# MusselGapeTracker_RevA_2.net
KiCad netlist of a schematic drawn in EAGLE
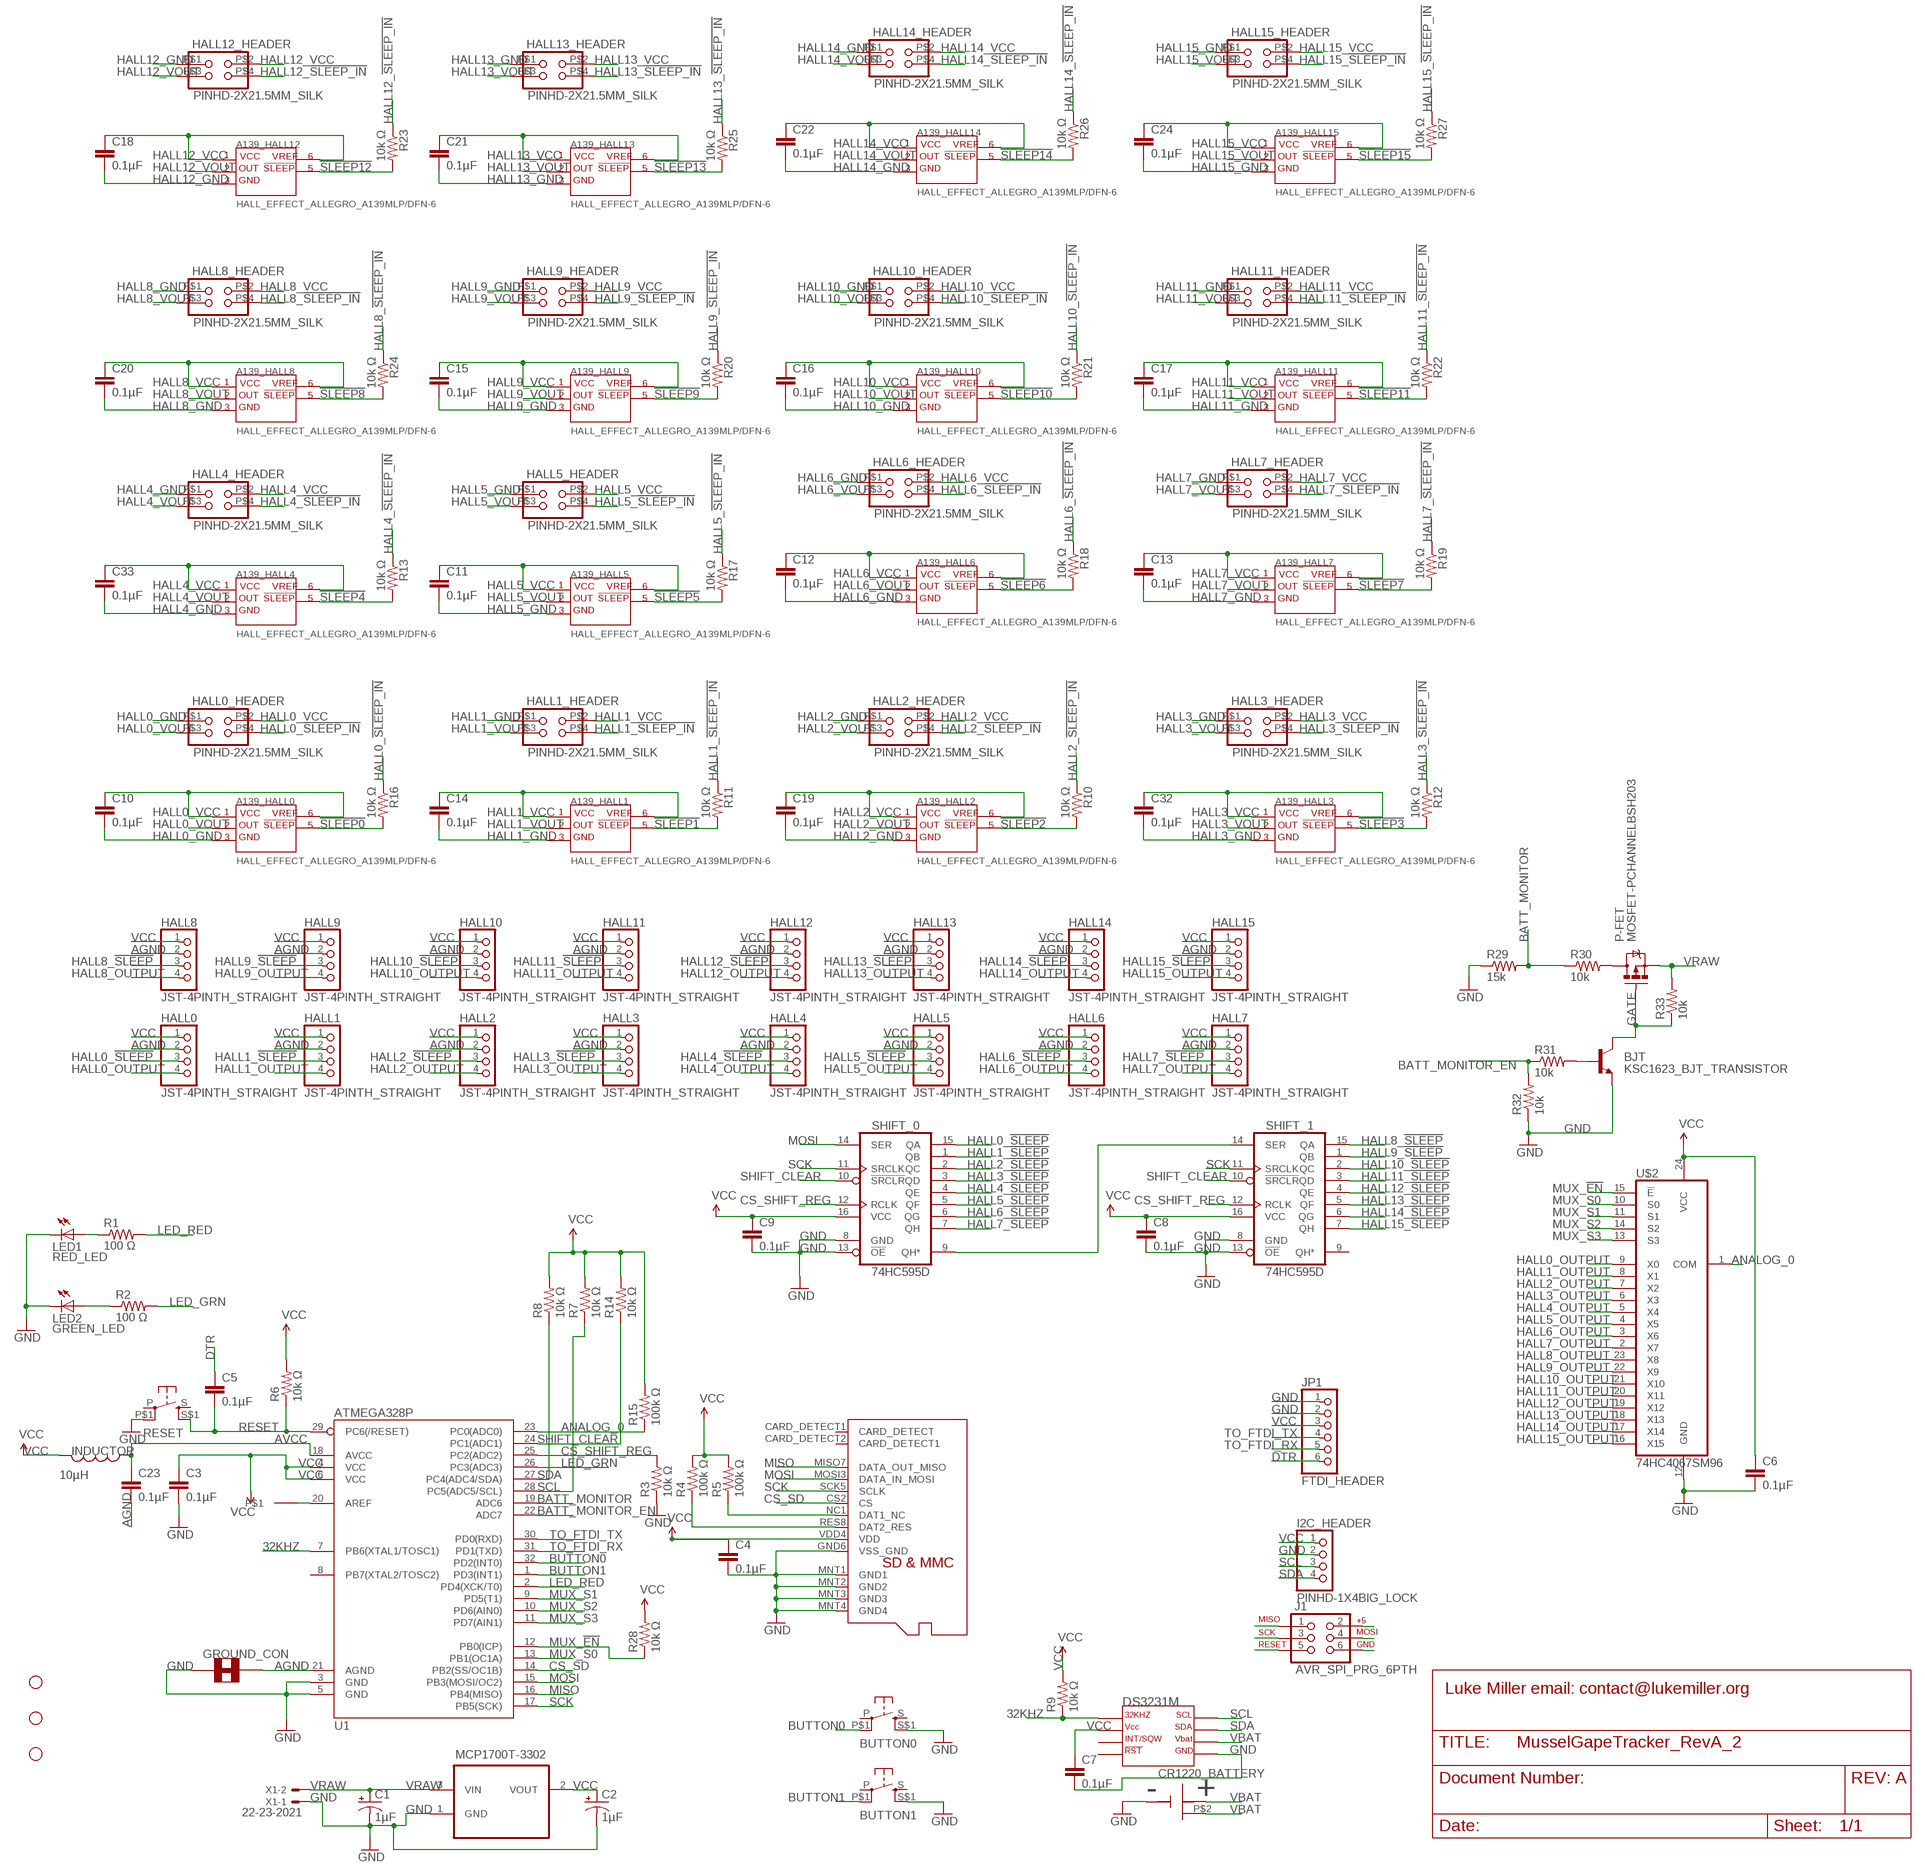
[diagram p0: schematic, sheet 1]

(export (version "E")
  (design (tool "Eeschema 10.0.6"))
  (components
    (comp (ref "A139_HALL0")
      (value "HALL_EFFECT_ALLEGRO_A139MLP/DFN-6")
      (footprint "eagle-import:A139__HALL_EFFECT")
      (libsource (lib "eagle-import") (part "HALL_EFFECT_ALLEGRO_A139MLP/DFN-6"))
    )
    (comp (ref "A139_HALL1")
      (value "HALL_EFFECT_ALLEGRO_A139MLP/DFN-6")
      (footprint "eagle-import:A139__HALL_EFFECT")
      (libsource (lib "eagle-import") (part "HALL_EFFECT_ALLEGRO_A139MLP/DFN-6"))
    )
    (comp (ref "A139_HALL2")
      (value "HALL_EFFECT_ALLEGRO_A139MLP/DFN-6")
      (footprint "eagle-import:A139__HALL_EFFECT")
      (libsource (lib "eagle-import") (part "HALL_EFFECT_ALLEGRO_A139MLP/DFN-6"))
    )
    (comp (ref "A139_HALL3")
      (value "HALL_EFFECT_ALLEGRO_A139MLP/DFN-6")
      (footprint "eagle-import:A139__HALL_EFFECT")
      (libsource (lib "eagle-import") (part "HALL_EFFECT_ALLEGRO_A139MLP/DFN-6"))
    )
    (comp (ref "A139_HALL4")
      (value "HALL_EFFECT_ALLEGRO_A139MLP/DFN-6")
      (footprint "eagle-import:A139__HALL_EFFECT")
      (libsource (lib "eagle-import") (part "HALL_EFFECT_ALLEGRO_A139MLP/DFN-6"))
    )
    (comp (ref "A139_HALL5")
      (value "HALL_EFFECT_ALLEGRO_A139MLP/DFN-6")
      (footprint "eagle-import:A139__HALL_EFFECT")
      (libsource (lib "eagle-import") (part "HALL_EFFECT_ALLEGRO_A139MLP/DFN-6"))
    )
    (comp (ref "A139_HALL6")
      (value "HALL_EFFECT_ALLEGRO_A139MLP/DFN-6")
      (footprint "eagle-import:A139__HALL_EFFECT")
      (libsource (lib "eagle-import") (part "HALL_EFFECT_ALLEGRO_A139MLP/DFN-6"))
    )
    (comp (ref "A139_HALL7")
      (value "HALL_EFFECT_ALLEGRO_A139MLP/DFN-6")
      (footprint "eagle-import:A139__HALL_EFFECT")
      (libsource (lib "eagle-import") (part "HALL_EFFECT_ALLEGRO_A139MLP/DFN-6"))
    )
    (comp (ref "A139_HALL8")
      (value "HALL_EFFECT_ALLEGRO_A139MLP/DFN-6")
      (footprint "eagle-import:A139__HALL_EFFECT")
      (libsource (lib "eagle-import") (part "HALL_EFFECT_ALLEGRO_A139MLP/DFN-6"))
    )
    (comp (ref "A139_HALL9")
      (value "HALL_EFFECT_ALLEGRO_A139MLP/DFN-6")
      (footprint "eagle-import:A139__HALL_EFFECT")
      (libsource (lib "eagle-import") (part "HALL_EFFECT_ALLEGRO_A139MLP/DFN-6"))
    )
    (comp (ref "A139_HALL10")
      (value "HALL_EFFECT_ALLEGRO_A139MLP/DFN-6")
      (footprint "eagle-import:A139__HALL_EFFECT")
      (libsource (lib "eagle-import") (part "HALL_EFFECT_ALLEGRO_A139MLP/DFN-6"))
    )
    (comp (ref "A139_HALL11")
      (value "HALL_EFFECT_ALLEGRO_A139MLP/DFN-6")
      (footprint "eagle-import:A139__HALL_EFFECT")
      (libsource (lib "eagle-import") (part "HALL_EFFECT_ALLEGRO_A139MLP/DFN-6"))
    )
    (comp (ref "A139_HALL12")
      (value "HALL_EFFECT_ALLEGRO_A139MLP/DFN-6")
      (footprint "eagle-import:A139__HALL_EFFECT")
      (libsource (lib "eagle-import") (part "HALL_EFFECT_ALLEGRO_A139MLP/DFN-6"))
    )
    (comp (ref "A139_HALL13")
      (value "HALL_EFFECT_ALLEGRO_A139MLP/DFN-6")
      (footprint "eagle-import:A139__HALL_EFFECT")
      (libsource (lib "eagle-import") (part "HALL_EFFECT_ALLEGRO_A139MLP/DFN-6"))
    )
    (comp (ref "A139_HALL14")
      (value "HALL_EFFECT_ALLEGRO_A139MLP/DFN-6")
      (footprint "eagle-import:A139__HALL_EFFECT")
      (libsource (lib "eagle-import") (part "HALL_EFFECT_ALLEGRO_A139MLP/DFN-6"))
    )
    (comp (ref "A139_HALL15")
      (value "HALL_EFFECT_ALLEGRO_A139MLP/DFN-6")
      (footprint "eagle-import:A139__HALL_EFFECT")
      (libsource (lib "eagle-import") (part "HALL_EFFECT_ALLEGRO_A139MLP/DFN-6"))
    )
    (comp (ref "BJT")
      (value "KSC1623_BJT_TRANSISTOR")
      (footprint "eagle-import:SOT23")
      (libsource (lib "eagle-import") (part "KSC1623_BJT_TRANSISTOR"))
    )
    (comp (ref "BUTTON0")
      (value "PUSHBUTTON_DPST_SMDSTANDARD")
      (footprint "eagle-import:PUSHBUTTON_DPST_SMD")
      (libsource (lib "eagle-import") (part "PUSHBUTTON_DPST_SMDSTANDARD"))
    )
    (comp (ref "BUTTON1")
      (value "PUSHBUTTON_DPST_SMDSTANDARD")
      (footprint "eagle-import:PUSHBUTTON_DPST_SMD")
      (libsource (lib "eagle-import") (part "PUSHBUTTON_DPST_SMDSTANDARD"))
    )
    (comp (ref "C1")
      (value "1µF")
      (footprint "eagle-import:PANASONIC_B")
      (libsource (lib "eagle-import") (part "CPOL-USB"))
    )
    (comp (ref "C2")
      (value "1µF")
      (footprint "eagle-import:PANASONIC_B")
      (libsource (lib "eagle-import") (part "CPOL-USB"))
    )
    (comp (ref "C3")
      (value "0.1µF")
      (footprint "eagle-import:0603")
      (libsource (lib "eagle-import") (part "CAP0603"))
    )
    (comp (ref "C4")
      (value "0.1µF")
      (footprint "eagle-import:0603")
      (libsource (lib "eagle-import") (part "CAP0603"))
    )
    (comp (ref "C5")
      (value "0.1µF")
      (footprint "eagle-import:0603")
      (libsource (lib "eagle-import") (part "CAP0603"))
    )
    (comp (ref "C6")
      (value "0.1µF")
      (footprint "eagle-import:0603")
      (libsource (lib "eagle-import") (part "CAP0603"))
    )
    (comp (ref "C7")
      (value "0.1µF")
      (footprint "eagle-import:0603")
      (libsource (lib "eagle-import") (part "CAP0603"))
    )
    (comp (ref "C8")
      (value "0.1µF")
      (footprint "eagle-import:0603")
      (libsource (lib "eagle-import") (part "CAP0603"))
    )
    (comp (ref "C9")
      (value "0.1µF")
      (footprint "eagle-import:0603")
      (libsource (lib "eagle-import") (part "CAP0603"))
    )
    (comp (ref "C10")
      (value "0.1µF")
      (footprint "eagle-import:0603")
      (libsource (lib "eagle-import") (part "CAP0603"))
    )
    (comp (ref "C11")
      (value "0.1µF")
      (footprint "eagle-import:0603")
      (libsource (lib "eagle-import") (part "CAP0603"))
    )
    (comp (ref "C12")
      (value "0.1µF")
      (footprint "eagle-import:0603")
      (libsource (lib "eagle-import") (part "CAP0603"))
    )
    (comp (ref "C13")
      (value "0.1µF")
      (footprint "eagle-import:0603")
      (libsource (lib "eagle-import") (part "CAP0603"))
    )
    (comp (ref "C14")
      (value "0.1µF")
      (footprint "eagle-import:0603")
      (libsource (lib "eagle-import") (part "CAP0603"))
    )
    (comp (ref "C15")
      (value "0.1µF")
      (footprint "eagle-import:0603")
      (libsource (lib "eagle-import") (part "CAP0603"))
    )
    (comp (ref "C16")
      (value "0.1µF")
      (footprint "eagle-import:0603")
      (libsource (lib "eagle-import") (part "CAP0603"))
    )
    (comp (ref "C17")
      (value "0.1µF")
      (footprint "eagle-import:0603")
      (libsource (lib "eagle-import") (part "CAP0603"))
    )
    (comp (ref "C18")
      (value "0.1µF")
      (footprint "eagle-import:0603")
      (libsource (lib "eagle-import") (part "CAP0603"))
    )
    (comp (ref "C19")
      (value "0.1µF")
      (footprint "eagle-import:0603")
      (libsource (lib "eagle-import") (part "CAP0603"))
    )
    (comp (ref "C20")
      (value "0.1µF")
      (footprint "eagle-import:0603")
      (libsource (lib "eagle-import") (part "CAP0603"))
    )
    (comp (ref "C21")
      (value "0.1µF")
      (footprint "eagle-import:0603")
      (libsource (lib "eagle-import") (part "CAP0603"))
    )
    (comp (ref "C22")
      (value "0.1µF")
      (footprint "eagle-import:0603")
      (libsource (lib "eagle-import") (part "CAP0603"))
    )
    (comp (ref "C23")
      (value "0.1µF")
      (footprint "eagle-import:0603")
      (libsource (lib "eagle-import") (part "CAP0603"))
    )
    (comp (ref "C24")
      (value "0.1µF")
      (footprint "eagle-import:0603")
      (libsource (lib "eagle-import") (part "CAP0603"))
    )
    (comp (ref "C32")
      (value "0.1µF")
      (footprint "eagle-import:0603")
      (libsource (lib "eagle-import") (part "CAP0603"))
    )
    (comp (ref "C33")
      (value "0.1µF")
      (footprint "eagle-import:0603")
      (libsource (lib "eagle-import") (part "CAP0603"))
    )
    (comp (ref "CR1220_BATTERY")
      (value "CR1220_BATTERY_HOLDERSMD")
      (footprint "eagle-import:CR1220_BATTERY_HOLDER_SMD")
      (libsource (lib "eagle-import") (part "CR1220_BATTERY_HOLDERSMD"))
    )
    (comp (ref "DS3231M")
      (value "DS3231MSOIC-8")
      (footprint "eagle-import:DS3231M_SOIC8")
      (libsource (lib "eagle-import") (part "DS3231MSOIC-8"))
    )
    (comp (ref "GROUND_CON")
      (value "SOLDER_JUMPER_TRACESTANDARD")
      (footprint "eagle-import:SJ_2S-TRACE")
      (libsource (lib "eagle-import") (part "SOLDER_JUMPER_TRACESTANDARD"))
    )
    (comp (ref "HALL0")
      (value "JST-4PINTH_STRAIGHT")
      (footprint "eagle-import:JST-PH-4-THM")
      (libsource (lib "eagle-import") (part "JST-4PINTH_STRAIGHT"))
    )
    (comp (ref "HALL0_HEADER")
      (value "PINHD-2X21.5MM_SILK")
      (footprint "eagle-import:2X2_1.5MM")
      (libsource (lib "eagle-import") (part "PINHD-2X21.5MM_SILK"))
    )
    (comp (ref "HALL1")
      (value "JST-4PINTH_STRAIGHT")
      (footprint "eagle-import:JST-PH-4-THM")
      (libsource (lib "eagle-import") (part "JST-4PINTH_STRAIGHT"))
    )
    (comp (ref "HALL1_HEADER")
      (value "PINHD-2X21.5MM_SILK")
      (footprint "eagle-import:2X2_1.5MM")
      (libsource (lib "eagle-import") (part "PINHD-2X21.5MM_SILK"))
    )
    (comp (ref "HALL2")
      (value "JST-4PINTH_STRAIGHT")
      (footprint "eagle-import:JST-PH-4-THM")
      (libsource (lib "eagle-import") (part "JST-4PINTH_STRAIGHT"))
    )
    (comp (ref "HALL2_HEADER")
      (value "PINHD-2X21.5MM_SILK")
      (footprint "eagle-import:2X2_1.5MM")
      (libsource (lib "eagle-import") (part "PINHD-2X21.5MM_SILK"))
    )
    (comp (ref "HALL3")
      (value "JST-4PINTH_STRAIGHT")
      (footprint "eagle-import:JST-PH-4-THM")
      (libsource (lib "eagle-import") (part "JST-4PINTH_STRAIGHT"))
    )
    (comp (ref "HALL3_HEADER")
      (value "PINHD-2X21.5MM_SILK")
      (footprint "eagle-import:2X2_1.5MM")
      (libsource (lib "eagle-import") (part "PINHD-2X21.5MM_SILK"))
    )
    (comp (ref "HALL4")
      (value "JST-4PINTH_STRAIGHT")
      (footprint "eagle-import:JST-PH-4-THM")
      (libsource (lib "eagle-import") (part "JST-4PINTH_STRAIGHT"))
    )
    (comp (ref "HALL4_HEADER")
      (value "PINHD-2X21.5MM_SILK")
      (footprint "eagle-import:2X2_1.5MM")
      (libsource (lib "eagle-import") (part "PINHD-2X21.5MM_SILK"))
    )
    (comp (ref "HALL5")
      (value "JST-4PINTH_STRAIGHT")
      (footprint "eagle-import:JST-PH-4-THM")
      (libsource (lib "eagle-import") (part "JST-4PINTH_STRAIGHT"))
    )
    (comp (ref "HALL5_HEADER")
      (value "PINHD-2X21.5MM_SILK")
      (footprint "eagle-import:2X2_1.5MM")
      (libsource (lib "eagle-import") (part "PINHD-2X21.5MM_SILK"))
    )
    (comp (ref "HALL6")
      (value "JST-4PINTH_STRAIGHT")
      (footprint "eagle-import:JST-PH-4-THM")
      (libsource (lib "eagle-import") (part "JST-4PINTH_STRAIGHT"))
    )
    (comp (ref "HALL6_HEADER")
      (value "PINHD-2X21.5MM_SILK")
      (footprint "eagle-import:2X2_1.5MM")
      (libsource (lib "eagle-import") (part "PINHD-2X21.5MM_SILK"))
    )
    (comp (ref "HALL7")
      (value "JST-4PINTH_STRAIGHT")
      (footprint "eagle-import:JST-PH-4-THM")
      (libsource (lib "eagle-import") (part "JST-4PINTH_STRAIGHT"))
    )
    (comp (ref "HALL7_HEADER")
      (value "PINHD-2X21.5MM_SILK")
      (footprint "eagle-import:2X2_1.5MM")
      (libsource (lib "eagle-import") (part "PINHD-2X21.5MM_SILK"))
    )
    (comp (ref "HALL8")
      (value "JST-4PINTH_STRAIGHT")
      (footprint "eagle-import:JST-PH-4-THM")
      (libsource (lib "eagle-import") (part "JST-4PINTH_STRAIGHT"))
    )
    (comp (ref "HALL8_HEADER")
      (value "PINHD-2X21.5MM_SILK")
      (footprint "eagle-import:2X2_1.5MM")
      (libsource (lib "eagle-import") (part "PINHD-2X21.5MM_SILK"))
    )
    (comp (ref "HALL9")
      (value "JST-4PINTH_STRAIGHT")
      (footprint "eagle-import:JST-PH-4-THM")
      (libsource (lib "eagle-import") (part "JST-4PINTH_STRAIGHT"))
    )
    (comp (ref "HALL9_HEADER")
      (value "PINHD-2X21.5MM_SILK")
      (footprint "eagle-import:2X2_1.5MM")
      (libsource (lib "eagle-import") (part "PINHD-2X21.5MM_SILK"))
    )
    (comp (ref "HALL10")
      (value "JST-4PINTH_STRAIGHT")
      (footprint "eagle-import:JST-PH-4-THM")
      (libsource (lib "eagle-import") (part "JST-4PINTH_STRAIGHT"))
    )
    (comp (ref "HALL10_HEADER")
      (value "PINHD-2X21.5MM_SILK")
      (footprint "eagle-import:2X2_1.5MM")
      (libsource (lib "eagle-import") (part "PINHD-2X21.5MM_SILK"))
    )
    (comp (ref "HALL11")
      (value "JST-4PINTH_STRAIGHT")
      (footprint "eagle-import:JST-PH-4-THM")
      (libsource (lib "eagle-import") (part "JST-4PINTH_STRAIGHT"))
    )
    (comp (ref "HALL11_HEADER")
      (value "PINHD-2X21.5MM_SILK")
      (footprint "eagle-import:2X2_1.5MM")
      (libsource (lib "eagle-import") (part "PINHD-2X21.5MM_SILK"))
    )
    (comp (ref "HALL12")
      (value "JST-4PINTH_STRAIGHT")
      (footprint "eagle-import:JST-PH-4-THM")
      (libsource (lib "eagle-import") (part "JST-4PINTH_STRAIGHT"))
    )
    (comp (ref "HALL12_HEADER")
      (value "PINHD-2X21.5MM_SILK")
      (footprint "eagle-import:2X2_1.5MM")
      (libsource (lib "eagle-import") (part "PINHD-2X21.5MM_SILK"))
    )
    (comp (ref "HALL13")
      (value "JST-4PINTH_STRAIGHT")
      (footprint "eagle-import:JST-PH-4-THM")
      (libsource (lib "eagle-import") (part "JST-4PINTH_STRAIGHT"))
    )
    (comp (ref "HALL13_HEADER")
      (value "PINHD-2X21.5MM_SILK")
      (footprint "eagle-import:2X2_1.5MM")
      (libsource (lib "eagle-import") (part "PINHD-2X21.5MM_SILK"))
    )
    (comp (ref "HALL14")
      (value "JST-4PINTH_STRAIGHT")
      (footprint "eagle-import:JST-PH-4-THM")
      (libsource (lib "eagle-import") (part "JST-4PINTH_STRAIGHT"))
    )
    (comp (ref "HALL14_HEADER")
      (value "PINHD-2X21.5MM_SILK")
      (footprint "eagle-import:2X2_1.5MM")
      (libsource (lib "eagle-import") (part "PINHD-2X21.5MM_SILK"))
    )
    (comp (ref "HALL15")
      (value "JST-4PINTH_STRAIGHT")
      (footprint "eagle-import:JST-PH-4-THM")
      (libsource (lib "eagle-import") (part "JST-4PINTH_STRAIGHT"))
    )
    (comp (ref "HALL15_HEADER")
      (value "PINHD-2X21.5MM_SILK")
      (footprint "eagle-import:2X2_1.5MM")
      (libsource (lib "eagle-import") (part "PINHD-2X21.5MM_SILK"))
    )
    (comp (ref "I2C_HEADER")
      (value "PINHD-1X4BIG_LOCK")
      (footprint "eagle-import:1X04_BIGLOCK")
      (libsource (lib "eagle-import") (part "PINHD-1X4BIG_LOCK"))
    )
    (comp (ref "INDUCTOR")
      (value "10µH")
      (footprint "eagle-import:I_0805")
      (libsource (lib "eagle-import") (part "INDUCTOR0805_TY"))
    )
    (comp (ref "J1")
      (value "AVR_SPI_PRG_6PTH")
      (footprint "eagle-import:2X3")
      (libsource (lib "eagle-import") (part "AVR_SPI_PRG_6PTH"))
    )
    (comp (ref "JP1")
      (value "FTDI_HEADER")
      (footprint "eagle-import:1X06-BIGLOCK")
      (libsource (lib "eagle-import") (part "PINHD-1X6LOCK"))
    )
    (comp (ref "LED1")
      (value "RED_LED")
      (footprint "eagle-import:CHIPLED_0805")
      (libsource (lib "eagle-import") (part "LED0805"))
    )
    (comp (ref "LED2")
      (value "GREEN_LED")
      (footprint "eagle-import:CHIPLED_0805")
      (libsource (lib "eagle-import") (part "LED0805"))
    )
    (comp (ref "MCP1700T-3302")
      (value "MCP1700T-3302E/TT")
      (footprint "eagle-import:SOT95P237X112-3N")
      (libsource (lib "eagle-import") (part "MCP1700T-3302E/TT"))
    )
    (comp (ref "P-FET")
      (value "MOSFET-PCHANNELBSH203")
      (footprint "eagle-import:SOT23-3")
      (libsource (lib "eagle-import") (part "MOSFET-PCHANNELBSH203"))
    )
    (comp (ref "R1")
      (value "100 Ω")
      (footprint "eagle-import:R0603")
      (libsource (lib "eagle-import") (part "RESISTOR_SMDR0603"))
    )
    (comp (ref "R2")
      (value "100 Ω")
      (footprint "eagle-import:R0603")
      (libsource (lib "eagle-import") (part "RESISTOR_SMDR0603"))
    )
    (comp (ref "R3")
      (value "10k Ω")
      (footprint "eagle-import:R0603")
      (libsource (lib "eagle-import") (part "RESISTOR_SMDR0603"))
    )
    (comp (ref "R4")
      (value "100k Ω")
      (footprint "eagle-import:R0603")
      (libsource (lib "eagle-import") (part "RESISTOR_SMDR0603"))
    )
    (comp (ref "R5")
      (value "100k Ω")
      (footprint "eagle-import:R0603")
      (libsource (lib "eagle-import") (part "RESISTOR_SMDR0603"))
    )
    (comp (ref "R6")
      (value "10k Ω")
      (footprint "eagle-import:R0603")
      (libsource (lib "eagle-import") (part "RESISTOR_SMDR0603"))
    )
    (comp (ref "R7")
      (value "10k Ω")
      (footprint "eagle-import:R0603")
      (libsource (lib "eagle-import") (part "RESISTOR_SMDR0603"))
    )
    (comp (ref "R8")
      (value "10k Ω")
      (footprint "eagle-import:R0603")
      (libsource (lib "eagle-import") (part "RESISTOR_SMDR0603"))
    )
    (comp (ref "R9")
      (value "10k Ω")
      (footprint "eagle-import:R0603")
      (libsource (lib "eagle-import") (part "RESISTOR_SMDR0603"))
    )
    (comp (ref "R10")
      (value "10k Ω")
      (footprint "eagle-import:R0603")
      (libsource (lib "eagle-import") (part "RESISTOR_SMDR0603"))
    )
    (comp (ref "R11")
      (value "10k Ω")
      (footprint "eagle-import:R0603")
      (libsource (lib "eagle-import") (part "RESISTOR_SMDR0603"))
    )
    (comp (ref "R12")
      (value "10k Ω")
      (footprint "eagle-import:R0603")
      (libsource (lib "eagle-import") (part "RESISTOR_SMDR0603"))
    )
    (comp (ref "R13")
      (value "10k Ω")
      (footprint "eagle-import:R0603")
      (libsource (lib "eagle-import") (part "RESISTOR_SMDR0603"))
    )
    (comp (ref "R14")
      (value "10k Ω")
      (footprint "eagle-import:R0603")
      (libsource (lib "eagle-import") (part "RESISTOR_SMDR0603"))
    )
    (comp (ref "R15")
      (value "100k Ω")
      (footprint "eagle-import:R0603")
      (libsource (lib "eagle-import") (part "RESISTOR_SMDR0603"))
    )
    (comp (ref "R16")
      (value "10k Ω")
      (footprint "eagle-import:R0603")
      (libsource (lib "eagle-import") (part "RESISTOR_SMDR0603"))
    )
    (comp (ref "R17")
      (value "10k Ω")
      (footprint "eagle-import:R0603")
      (libsource (lib "eagle-import") (part "RESISTOR_SMDR0603"))
    )
    (comp (ref "R18")
      (value "10k Ω")
      (footprint "eagle-import:R0603")
      (libsource (lib "eagle-import") (part "RESISTOR_SMDR0603"))
    )
    (comp (ref "R19")
      (value "10k Ω")
      (footprint "eagle-import:R0603")
      (libsource (lib "eagle-import") (part "RESISTOR_SMDR0603"))
    )
    (comp (ref "R20")
      (value "10k Ω")
      (footprint "eagle-import:R0603")
      (libsource (lib "eagle-import") (part "RESISTOR_SMDR0603"))
    )
    (comp (ref "R21")
      (value "10k Ω")
      (footprint "eagle-import:R0603")
      (libsource (lib "eagle-import") (part "RESISTOR_SMDR0603"))
    )
    (comp (ref "R22")
      (value "10k Ω")
      (footprint "eagle-import:R0603")
      (libsource (lib "eagle-import") (part "RESISTOR_SMDR0603"))
    )
    (comp (ref "R23")
      (value "10k Ω")
      (footprint "eagle-import:R0603")
      (libsource (lib "eagle-import") (part "RESISTOR_SMDR0603"))
    )
    (comp (ref "R24")
      (value "10k Ω")
      (footprint "eagle-import:R0603")
      (libsource (lib "eagle-import") (part "RESISTOR_SMDR0603"))
    )
    (comp (ref "R25")
      (value "10k Ω")
      (footprint "eagle-import:R0603")
      (libsource (lib "eagle-import") (part "RESISTOR_SMDR0603"))
    )
    (comp (ref "R26")
      (value "10k Ω")
      (footprint "eagle-import:R0603")
      (libsource (lib "eagle-import") (part "RESISTOR_SMDR0603"))
    )
    (comp (ref "R27")
      (value "10k Ω")
      (footprint "eagle-import:R0603")
      (libsource (lib "eagle-import") (part "RESISTOR_SMDR0603"))
    )
    (comp (ref "R28")
      (value "10k Ω")
      (footprint "eagle-import:R0603")
      (libsource (lib "eagle-import") (part "RESISTOR_SMDR0603"))
    )
    (comp (ref "R29")
      (value "15k")
      (footprint "eagle-import:R0603")
      (libsource (lib "eagle-import") (part "RESISTOR_SMDR0603"))
    )
    (comp (ref "R30")
      (value "10k")
      (footprint "eagle-import:R0603")
      (libsource (lib "eagle-import") (part "RESISTOR_SMDR0603"))
    )
    (comp (ref "R31")
      (value "10k")
      (footprint "eagle-import:R0603")
      (libsource (lib "eagle-import") (part "RESISTOR_SMDR0603"))
    )
    (comp (ref "R32")
      (value "10k")
      (footprint "eagle-import:R0603")
      (libsource (lib "eagle-import") (part "RESISTOR_SMDR0603"))
    )
    (comp (ref "R33")
      (value "10k")
      (footprint "eagle-import:R0603")
      (libsource (lib "eagle-import") (part "RESISTOR_SMDR0603"))
    )
    (comp (ref "RESET")
      (value "PUSHBUTTON_DPST_SMDSTANDARD")
      (footprint "eagle-import:PUSHBUTTON_DPST_SMD")
      (libsource (lib "eagle-import") (part "PUSHBUTTON_DPST_SMDSTANDARD"))
    )
    (comp (ref "SHIFT_0")
      (value "74HC595D")
      (footprint "eagle-import:SO16")
      (libsource (lib "eagle-import") (part "74HC595D"))
    )
    (comp (ref "SHIFT_1")
      (value "74HC595D")
      (footprint "eagle-import:SO16")
      (libsource (lib "eagle-import") (part "74HC595D"))
    )
    (comp (ref "STANDOFF1")
      (value "STAND-OFF")
      (footprint "eagle-import:STAND-OFF")
      (libsource (lib "eagle-import") (part "STAND-OFF"))
    )
    (comp (ref "STANDOFF2")
      (value "STAND-OFF")
      (footprint "eagle-import:STAND-OFF")
      (libsource (lib "eagle-import") (part "STAND-OFF"))
    )
    (comp (ref "STANDOFF3")
      (value "STAND-OFF")
      (footprint "eagle-import:STAND-OFF")
      (libsource (lib "eagle-import") (part "STAND-OFF"))
    )
    (comp (ref "U$1")
      (value "MICROSD_MOLEX_REVERSECURRENT")
      (footprint "eagle-import:MICROSD_SOCKET_MOLEX_REVERSEMOUNT")
      (libsource (lib "eagle-import") (part "MICROSD_MOLEX_REVERSECURRENT"))
    )
    (comp (ref "U$2")
      (value "74HC4067SM96")
      (footprint "eagle-import:SSOP24")
      (libsource (lib "eagle-import") (part "74HC4067SM96"))
    )
    (comp (ref "U$17")
      (value "PINHD-1X1SMALL")
      (footprint "eagle-import:1X01_SMALL")
      (libsource (lib "eagle-import") (part "PINHD-1X1SMALL"))
    )
    (comp (ref "U1")
      (value "ATMEGA328P")
      (footprint "eagle-import:TQFP32-08")
      (libsource (lib "eagle-import") (part "ATMEGA328_SMT"))
    )
    (comp (ref "X1")
      (value "22-23-2021")
      (footprint "eagle-import:22-23-2021")
      (fields (field (name "MF") "MOLEX"))
      (libsource (lib "eagle-import") (part "22-23-2021"))
    )
  )
  (nets
    (net (code "1") (name "/32KHZ") (class "Default")
      (node (ref "DS3231M") (pin "1") (pinfunction "P$1_32KHZ_1") (pintype "bidirectional"))
      (node (ref "R9") (pin "1") (pinfunction "1_1") (pintype "passive"))
      (node (ref "U1") (pin "7") (pinfunction "PB6(XTAL1/TOSC1)_7") (pintype "bidirectional"))
    )
    (net (code "2") (name "/AGND") (class "Default")
      (node (ref "C23") (pin "2") (pinfunction "2_2") (pintype "passive"))
      (node (ref "GROUND_CON") (pin "2") (pinfunction "P$2_2") (pintype "bidirectional"))
      (node (ref "HALL0") (pin "2") (pinfunction "2_2") (pintype "passive"))
      (node (ref "HALL1") (pin "2") (pinfunction "2_2") (pintype "passive"))
      (node (ref "HALL10") (pin "2") (pinfunction "2_2") (pintype "passive"))
      (node (ref "HALL11") (pin "2") (pinfunction "2_2") (pintype "passive"))
      (node (ref "HALL12") (pin "2") (pinfunction "2_2") (pintype "passive"))
      (node (ref "HALL13") (pin "2") (pinfunction "2_2") (pintype "passive"))
      (node (ref "HALL14") (pin "2") (pinfunction "2_2") (pintype "passive"))
      (node (ref "HALL15") (pin "2") (pinfunction "2_2") (pintype "passive"))
      (node (ref "HALL2") (pin "2") (pinfunction "2_2") (pintype "passive"))
      (node (ref "HALL3") (pin "2") (pinfunction "2_2") (pintype "passive"))
      (node (ref "HALL4") (pin "2") (pinfunction "2_2") (pintype "passive"))
      (node (ref "HALL5") (pin "2") (pinfunction "2_2") (pintype "passive"))
      (node (ref "HALL6") (pin "2") (pinfunction "2_2") (pintype "passive"))
      (node (ref "HALL7") (pin "2") (pinfunction "2_2") (pintype "passive"))
      (node (ref "HALL8") (pin "2") (pinfunction "2_2") (pintype "passive"))
      (node (ref "HALL9") (pin "2") (pinfunction "2_2") (pintype "passive"))
      (node (ref "U1") (pin "21") (pinfunction "AGND_21") (pintype "bidirectional"))
    )
    (net (code "3") (name "/ANALOG_0") (class "Default")
      (node (ref "R15") (pin "1") (pinfunction "1_1") (pintype "passive"))
      (node (ref "U$2") (pin "1") (pinfunction "COM_1") (pintype "output"))
      (node (ref "U1") (pin "23") (pinfunction "PC0(ADC0)_23") (pintype "bidirectional"))
    )
    (net (code "4") (name "/AVCC") (class "Default")
      (node (ref "C23") (pin "1") (pinfunction "1_1") (pintype "passive"))
      (node (ref "INDUCTOR") (pin "P$1") (pinfunction "1_P$1") (pintype "passive"))
      (node (ref "U1") (pin "18") (pinfunction "AVCC_18") (pintype "bidirectional"))
    )
    (net (code "5") (name "/BATT_MONITOR") (class "Default")
      (node (ref "R29") (pin "2") (pinfunction "2_2") (pintype "passive"))
      (node (ref "R30") (pin "1") (pinfunction "1_1") (pintype "passive"))
      (node (ref "U1") (pin "19") (pinfunction "ADC6_19") (pintype "bidirectional"))
    )
    (net (code "6") (name "/BATT_MONITOR_EN") (class "Default")
      (node (ref "R31") (pin "1") (pinfunction "1_1") (pintype "passive"))
      (node (ref "R32") (pin "2") (pinfunction "2_2") (pintype "passive"))
      (node (ref "U1") (pin "22") (pinfunction "ADC7_22") (pintype "bidirectional"))
    )
    (net (code "7") (name "/BUTTON0") (class "Default")
      (node (ref "BUTTON0") (pin "P$1") (pinfunction "P1_P$1") (pintype "passive"))
      (node (ref "U1") (pin "32") (pinfunction "PD2(INT0)_32") (pintype "bidirectional"))
    )
    (net (code "8") (name "/BUTTON1") (class "Default")
      (node (ref "BUTTON1") (pin "P$1") (pinfunction "P1_P$1") (pintype "passive"))
      (node (ref "U1") (pin "1") (pinfunction "PD3(INT1)_1") (pintype "bidirectional"))
    )
    (net (code "9") (name "/CS_SD") (class "Default")
      (node (ref "U$1") (pin "CS2") (pinfunction "CS_CS2") (pintype "input"))
      (node (ref "U1") (pin "14") (pinfunction "PB2(SS/OC1B)_14") (pintype "bidirectional"))
    )
    (net (code "10") (name "/CS_SHIFT_REG") (class "Default")
      (node (ref "R3") (pin "2") (pinfunction "2_2") (pintype "passive"))
      (node (ref "SHIFT_0") (pin "12") (pinfunction "RCLK_12") (pintype "input"))
      (node (ref "SHIFT_1") (pin "12") (pinfunction "RCLK_12") (pintype "input"))
      (node (ref "U1") (pin "25") (pinfunction "PC2(ADC2)_25") (pintype "bidirectional"))
    )
    (net (code "11") (name "/DTR") (class "Default")
      (node (ref "C5") (pin "1") (pinfunction "1_1") (pintype "passive"))
      (node (ref "JP1") (pin "6") (pinfunction "6_6") (pintype "passive"))
    )
    (net (code "12") (name "/GATE") (class "Default")
      (node (ref "BJT") (pin "3") (pinfunction "C_3") (pintype "passive"))
      (node (ref "P-FET") (pin "1") (pinfunction "G_1") (pintype "passive"))
      (node (ref "R33") (pin "1") (pinfunction "1_1") (pintype "passive"))
    )
    (net (code "13") (name "/HALL0_GND") (class "Default")
      (node (ref "A139_HALL0") (pin "P$3_4") (pinfunction "P$3_P$3_4") (pintype "bidirectional"))
      (node (ref "C10") (pin "2") (pinfunction "2_2") (pintype "passive"))
      (node (ref "HALL0_HEADER") (pin "P$1") (pinfunction "1_P$1") (pintype "passive"))
    )
    (net (code "14") (name "/HALL0_OUTPUT") (class "Default")
      (node (ref "HALL0") (pin "4") (pinfunction "4_4") (pintype "passive"))
      (node (ref "U$2") (pin "9") (pinfunction "X0_9") (pintype "input"))
    )
    (net (code "15") (name "/HALL0_VCC") (class "Default")
      (node (ref "A139_HALL0") (pin "P$1") (pinfunction "P$1_P$1") (pintype "bidirectional"))
      (node (ref "A139_HALL0") (pin "P$6") (pinfunction "P$6_P$6") (pintype "bidirectional"))
      (node (ref "C10") (pin "1") (pinfunction "1_1") (pintype "passive"))
      (node (ref "HALL0_HEADER") (pin "P$2") (pinfunction "2_P$2") (pintype "passive"))
    )
    (net (code "16") (name "/HALL0_VOUT") (class "Default")
      (node (ref "A139_HALL0") (pin "P$2") (pinfunction "P$2_P$2") (pintype "bidirectional"))
      (node (ref "HALL0_HEADER") (pin "P$3") (pinfunction "3_P$3") (pintype "passive"))
    )
    (net (code "17") (name "/HALL0_~{SLEEP_IN}") (class "Default")
      (node (ref "HALL0_HEADER") (pin "P$4") (pinfunction "4_P$4") (pintype "passive"))
      (node (ref "R16") (pin "1") (pinfunction "1_1") (pintype "passive"))
    )
    (net (code "18") (name "/HALL0_~{SLEEP}") (class "Default")
      (node (ref "HALL0") (pin "3") (pinfunction "3_3") (pintype "passive"))
      (node (ref "SHIFT_0") (pin "15") (pinfunction "QA_15") (pintype "tri_state"))
    )
    (net (code "19") (name "/HALL1_GND") (class "Default")
      (node (ref "A139_HALL1") (pin "P$3_4") (pinfunction "P$3_P$3_4") (pintype "bidirectional"))
      (node (ref "C14") (pin "2") (pinfunction "2_2") (pintype "passive"))
      (node (ref "HALL1_HEADER") (pin "P$1") (pinfunction "1_P$1") (pintype "passive"))
    )
    (net (code "20") (name "/HALL1_OUTPUT") (class "Default")
      (node (ref "HALL1") (pin "4") (pinfunction "4_4") (pintype "passive"))
      (node (ref "U$2") (pin "8") (pinfunction "X1_8") (pintype "input"))
    )
    (net (code "21") (name "/HALL1_VCC") (class "Default")
      (node (ref "A139_HALL1") (pin "P$1") (pinfunction "P$1_P$1") (pintype "bidirectional"))
      (node (ref "A139_HALL1") (pin "P$6") (pinfunction "P$6_P$6") (pintype "bidirectional"))
      (node (ref "C14") (pin "1") (pinfunction "1_1") (pintype "passive"))
      (node (ref "HALL1_HEADER") (pin "P$2") (pinfunction "2_P$2") (pintype "passive"))
    )
    (net (code "22") (name "/HALL1_VOUT") (class "Default")
      (node (ref "A139_HALL1") (pin "P$2") (pinfunction "P$2_P$2") (pintype "bidirectional"))
      (node (ref "HALL1_HEADER") (pin "P$3") (pinfunction "3_P$3") (pintype "passive"))
    )
    (net (code "23") (name "/HALL1_~{SLEEP_IN}") (class "Default")
      (node (ref "HALL1_HEADER") (pin "P$4") (pinfunction "4_P$4") (pintype "passive"))
      (node (ref "R11") (pin "1") (pinfunction "1_1") (pintype "passive"))
    )
    (net (code "24") (name "/HALL1_~{SLEEP}") (class "Default")
      (node (ref "HALL1") (pin "3") (pinfunction "3_3") (pintype "passive"))
      (node (ref "SHIFT_0") (pin "1") (pinfunction "QB_1") (pintype "tri_state"))
    )
    (net (code "25") (name "/HALL2_GND") (class "Default")
      (node (ref "A139_HALL2") (pin "P$3_4") (pinfunction "P$3_P$3_4") (pintype "bidirectional"))
      (node (ref "C19") (pin "2") (pinfunction "2_2") (pintype "passive"))
      (node (ref "HALL2_HEADER") (pin "P$1") (pinfunction "1_P$1") (pintype "passive"))
    )
    (net (code "26") (name "/HALL2_OUTPUT") (class "Default")
      (node (ref "HALL2") (pin "4") (pinfunction "4_4") (pintype "passive"))
      (node (ref "U$2") (pin "7") (pinfunction "X2_7") (pintype "input"))
    )
    (net (code "27") (name "/HALL2_VCC") (class "Default")
      (node (ref "A139_HALL2") (pin "P$1") (pinfunction "P$1_P$1") (pintype "bidirectional"))
      (node (ref "A139_HALL2") (pin "P$6") (pinfunction "P$6_P$6") (pintype "bidirectional"))
      (node (ref "C19") (pin "1") (pinfunction "1_1") (pintype "passive"))
      (node (ref "HALL2_HEADER") (pin "P$2") (pinfunction "2_P$2") (pintype "passive"))
    )
    (net (code "28") (name "/HALL2_VOUT") (class "Default")
      (node (ref "A139_HALL2") (pin "P$2") (pinfunction "P$2_P$2") (pintype "bidirectional"))
      (node (ref "HALL2_HEADER") (pin "P$3") (pinfunction "3_P$3") (pintype "passive"))
    )
    (net (code "29") (name "/HALL2_~{SLEEP_IN}") (class "Default")
      (node (ref "HALL2_HEADER") (pin "P$4") (pinfunction "4_P$4") (pintype "passive"))
      (node (ref "R10") (pin "1") (pinfunction "1_1") (pintype "passive"))
    )
    (net (code "30") (name "/HALL2_~{SLEEP}") (class "Default")
      (node (ref "HALL2") (pin "3") (pinfunction "3_3") (pintype "passive"))
      (node (ref "SHIFT_0") (pin "2") (pinfunction "QC_2") (pintype "tri_state"))
    )
    (net (code "31") (name "/HALL3_GND") (class "Default")
      (node (ref "A139_HALL3") (pin "P$3_4") (pinfunction "P$3_P$3_4") (pintype "bidirectional"))
      (node (ref "C32") (pin "2") (pinfunction "2_2") (pintype "passive"))
      (node (ref "HALL3_HEADER") (pin "P$1") (pinfunction "1_P$1") (pintype "passive"))
    )
    (net (code "32") (name "/HALL3_OUTPUT") (class "Default")
      (node (ref "HALL3") (pin "4") (pinfunction "4_4") (pintype "passive"))
      (node (ref "U$2") (pin "6") (pinfunction "X3_6") (pintype "input"))
    )
    (net (code "33") (name "/HALL3_VCC") (class "Default")
      (node (ref "A139_HALL3") (pin "P$1") (pinfunction "P$1_P$1") (pintype "bidirectional"))
      (node (ref "A139_HALL3") (pin "P$6") (pinfunction "P$6_P$6") (pintype "bidirectional"))
      (node (ref "C32") (pin "1") (pinfunction "1_1") (pintype "passive"))
      (node (ref "HALL3_HEADER") (pin "P$2") (pinfunction "2_P$2") (pintype "passive"))
    )
    (net (code "34") (name "/HALL3_VOUT") (class "Default")
      (node (ref "A139_HALL3") (pin "P$2") (pinfunction "P$2_P$2") (pintype "bidirectional"))
      (node (ref "HALL3_HEADER") (pin "P$3") (pinfunction "3_P$3") (pintype "passive"))
    )
    (net (code "35") (name "/HALL3_~{SLEEP_IN}") (class "Default")
      (node (ref "HALL3_HEADER") (pin "P$4") (pinfunction "4_P$4") (pintype "passive"))
      (node (ref "R12") (pin "1") (pinfunction "1_1") (pintype "passive"))
    )
    (net (code "36") (name "/HALL3_~{SLEEP}") (class "Default")
      (node (ref "HALL3") (pin "3") (pinfunction "3_3") (pintype "passive"))
      (node (ref "SHIFT_0") (pin "3") (pinfunction "QD_3") (pintype "tri_state"))
    )
    (net (code "37") (name "/HALL4_GND") (class "Default")
      (node (ref "A139_HALL4") (pin "P$3_4") (pinfunction "P$3_P$3_4") (pintype "bidirectional"))
      (node (ref "C33") (pin "2") (pinfunction "2_2") (pintype "passive"))
      (node (ref "HALL4_HEADER") (pin "P$1") (pinfunction "1_P$1") (pintype "passive"))
    )
    (net (code "38") (name "/HALL4_OUTPUT") (class "Default")
      (node (ref "HALL4") (pin "4") (pinfunction "4_4") (pintype "passive"))
      (node (ref "U$2") (pin "5") (pinfunction "X4_5") (pintype "input"))
    )
    (net (code "39") (name "/HALL4_VCC") (class "Default")
      (node (ref "A139_HALL4") (pin "P$1") (pinfunction "P$1_P$1") (pintype "bidirectional"))
      (node (ref "A139_HALL4") (pin "P$6") (pinfunction "P$6_P$6") (pintype "bidirectional"))
      (node (ref "C33") (pin "1") (pinfunction "1_1") (pintype "passive"))
      (node (ref "HALL4_HEADER") (pin "P$2") (pinfunction "2_P$2") (pintype "passive"))
    )
    (net (code "40") (name "/HALL4_VOUT") (class "Default")
      (node (ref "A139_HALL4") (pin "P$2") (pinfunction "P$2_P$2") (pintype "bidirectional"))
      (node (ref "HALL4_HEADER") (pin "P$3") (pinfunction "3_P$3") (pintype "passive"))
    )
    (net (code "41") (name "/HALL4_~{SLEEP_IN}") (class "Default")
      (node (ref "HALL4_HEADER") (pin "P$4") (pinfunction "4_P$4") (pintype "passive"))
      (node (ref "R13") (pin "1") (pinfunction "1_1") (pintype "passive"))
    )
    (net (code "42") (name "/HALL4_~{SLEEP}") (class "Default")
      (node (ref "HALL4") (pin "3") (pinfunction "3_3") (pintype "passive"))
      (node (ref "SHIFT_0") (pin "4") (pinfunction "QE_4") (pintype "tri_state"))
    )
    (net (code "43") (name "/HALL5_GND") (class "Default")
      (node (ref "A139_HALL5") (pin "P$3_4") (pinfunction "P$3_P$3_4") (pintype "bidirectional"))
      (node (ref "C11") (pin "2") (pinfunction "2_2") (pintype "passive"))
      (node (ref "HALL5_HEADER") (pin "P$1") (pinfunction "1_P$1") (pintype "passive"))
    )
    (net (code "44") (name "/HALL5_OUTPUT") (class "Default")
      (node (ref "HALL5") (pin "4") (pinfunction "4_4") (pintype "passive"))
      (node (ref "U$2") (pin "4") (pinfunction "X5_4") (pintype "input"))
    )
    (net (code "45") (name "/HALL5_VCC") (class "Default")
      (node (ref "A139_HALL5") (pin "P$1") (pinfunction "P$1_P$1") (pintype "bidirectional"))
      (node (ref "A139_HALL5") (pin "P$6") (pinfunction "P$6_P$6") (pintype "bidirectional"))
      (node (ref "C11") (pin "1") (pinfunction "1_1") (pintype "passive"))
      (node (ref "HALL5_HEADER") (pin "P$2") (pinfunction "2_P$2") (pintype "passive"))
    )
    (net (code "46") (name "/HALL5_VOUT") (class "Default")
      (node (ref "A139_HALL5") (pin "P$2") (pinfunction "P$2_P$2") (pintype "bidirectional"))
      (node (ref "HALL5_HEADER") (pin "P$3") (pinfunction "3_P$3") (pintype "passive"))
    )
    (net (code "47") (name "/HALL5_~{SLEEP_IN}") (class "Default")
      (node (ref "HALL5_HEADER") (pin "P$4") (pinfunction "4_P$4") (pintype "passive"))
      (node (ref "R17") (pin "1") (pinfunction "1_1") (pintype "passive"))
    )
    (net (code "48") (name "/HALL5_~{SLEEP}") (class "Default")
      (node (ref "HALL5") (pin "3") (pinfunction "3_3") (pintype "passive"))
      (node (ref "SHIFT_0") (pin "5") (pinfunction "QF_5") (pintype "tri_state"))
    )
    (net (code "49") (name "/HALL6_GND") (class "Default")
      (node (ref "A139_HALL6") (pin "P$3_4") (pinfunction "P$3_P$3_4") (pintype "bidirectional"))
      (node (ref "C12") (pin "2") (pinfunction "2_2") (pintype "passive"))
      (node (ref "HALL6_HEADER") (pin "P$1") (pinfunction "1_P$1") (pintype "passive"))
    )
    (net (code "50") (name "/HALL6_OUTPUT") (class "Default")
      (node (ref "HALL6") (pin "4") (pinfunction "4_4") (pintype "passive"))
      (node (ref "U$2") (pin "3") (pinfunction "X6_3") (pintype "input"))
    )
    (net (code "51") (name "/HALL6_VCC") (class "Default")
      (node (ref "A139_HALL6") (pin "P$1") (pinfunction "P$1_P$1") (pintype "bidirectional"))
      (node (ref "A139_HALL6") (pin "P$6") (pinfunction "P$6_P$6") (pintype "bidirectional"))
      (node (ref "C12") (pin "1") (pinfunction "1_1") (pintype "passive"))
      (node (ref "HALL6_HEADER") (pin "P$2") (pinfunction "2_P$2") (pintype "passive"))
    )
    (net (code "52") (name "/HALL6_VOUT") (class "Default")
      (node (ref "A139_HALL6") (pin "P$2") (pinfunction "P$2_P$2") (pintype "bidirectional"))
      (node (ref "HALL6_HEADER") (pin "P$3") (pinfunction "3_P$3") (pintype "passive"))
    )
    (net (code "53") (name "/HALL6_~{SLEEP_IN}") (class "Default")
      (node (ref "HALL6_HEADER") (pin "P$4") (pinfunction "4_P$4") (pintype "passive"))
      (node (ref "R18") (pin "1") (pinfunction "1_1") (pintype "passive"))
    )
    (net (code "54") (name "/HALL6_~{SLEEP}") (class "Default")
      (node (ref "HALL6") (pin "3") (pinfunction "3_3") (pintype "passive"))
      (node (ref "SHIFT_0") (pin "6") (pinfunction "QG_6") (pintype "tri_state"))
    )
    (net (code "55") (name "/HALL7_GND") (class "Default")
      (node (ref "A139_HALL7") (pin "P$3_4") (pinfunction "P$3_P$3_4") (pintype "bidirectional"))
      (node (ref "C13") (pin "2") (pinfunction "2_2") (pintype "passive"))
      (node (ref "HALL7_HEADER") (pin "P$1") (pinfunction "1_P$1") (pintype "passive"))
    )
    (net (code "56") (name "/HALL7_OUTPUT") (class "Default")
      (node (ref "HALL7") (pin "4") (pinfunction "4_4") (pintype "passive"))
      (node (ref "U$2") (pin "2") (pinfunction "X7_2") (pintype "input"))
    )
    (net (code "57") (name "/HALL7_VCC") (class "Default")
      (node (ref "A139_HALL7") (pin "P$1") (pinfunction "P$1_P$1") (pintype "bidirectional"))
      (node (ref "A139_HALL7") (pin "P$6") (pinfunction "P$6_P$6") (pintype "bidirectional"))
      (node (ref "C13") (pin "1") (pinfunction "1_1") (pintype "passive"))
      (node (ref "HALL7_HEADER") (pin "P$2") (pinfunction "2_P$2") (pintype "passive"))
    )
    (net (code "58") (name "/HALL7_VOUT") (class "Default")
      (node (ref "A139_HALL7") (pin "P$2") (pinfunction "P$2_P$2") (pintype "bidirectional"))
      (node (ref "HALL7_HEADER") (pin "P$3") (pinfunction "3_P$3") (pintype "passive"))
    )
    (net (code "59") (name "/HALL7_~{SLEEP_IN}") (class "Default")
      (node (ref "HALL7_HEADER") (pin "P$4") (pinfunction "4_P$4") (pintype "passive"))
      (node (ref "R19") (pin "1") (pinfunction "1_1") (pintype "passive"))
    )
    (net (code "60") (name "/HALL7_~{SLEEP}") (class "Default")
      (node (ref "HALL7") (pin "3") (pinfunction "3_3") (pintype "passive"))
      (node (ref "SHIFT_0") (pin "7") (pinfunction "QH_7") (pintype "tri_state"))
    )
    (net (code "61") (name "/HALL8_GND") (class "Default")
      (node (ref "A139_HALL8") (pin "P$3_4") (pinfunction "P$3_P$3_4") (pintype "bidirectional"))
      (node (ref "C20") (pin "2") (pinfunction "2_2") (pintype "passive"))
      (node (ref "HALL8_HEADER") (pin "P$1") (pinfunction "1_P$1") (pintype "passive"))
    )
    (net (code "62") (name "/HALL8_OUTPUT") (class "Default")
      (node (ref "HALL8") (pin "4") (pinfunction "4_4") (pintype "passive"))
      (node (ref "U$2") (pin "23") (pinfunction "X8_23") (pintype "input"))
    )
    (net (code "63") (name "/HALL8_VCC") (class "Default")
      (node (ref "A139_HALL8") (pin "P$1") (pinfunction "P$1_P$1") (pintype "bidirectional"))
      (node (ref "A139_HALL8") (pin "P$6") (pinfunction "P$6_P$6") (pintype "bidirectional"))
      (node (ref "C20") (pin "1") (pinfunction "1_1") (pintype "passive"))
      (node (ref "HALL8_HEADER") (pin "P$2") (pinfunction "2_P$2") (pintype "passive"))
    )
    (net (code "64") (name "/HALL8_VOUT") (class "Default")
      (node (ref "A139_HALL8") (pin "P$2") (pinfunction "P$2_P$2") (pintype "bidirectional"))
      (node (ref "HALL8_HEADER") (pin "P$3") (pinfunction "3_P$3") (pintype "passive"))
    )
    (net (code "65") (name "/HALL8_~{SLEEP_IN}") (class "Default")
      (node (ref "HALL8_HEADER") (pin "P$4") (pinfunction "4_P$4") (pintype "passive"))
      (node (ref "R24") (pin "1") (pinfunction "1_1") (pintype "passive"))
    )
    (net (code "66") (name "/HALL8_~{SLEEP}") (class "Default")
      (node (ref "HALL8") (pin "3") (pinfunction "3_3") (pintype "passive"))
      (node (ref "SHIFT_1") (pin "15") (pinfunction "QA_15") (pintype "tri_state"))
    )
    (net (code "67") (name "/HALL9_GND") (class "Default")
      (node (ref "A139_HALL9") (pin "P$3_4") (pinfunction "P$3_P$3_4") (pintype "bidirectional"))
      (node (ref "C15") (pin "2") (pinfunction "2_2") (pintype "passive"))
      (node (ref "HALL9_HEADER") (pin "P$1") (pinfunction "1_P$1") (pintype "passive"))
    )
    (net (code "68") (name "/HALL9_OUTPUT") (class "Default")
      (node (ref "HALL9") (pin "4") (pinfunction "4_4") (pintype "passive"))
      (node (ref "U$2") (pin "22") (pinfunction "X9_22") (pintype "input"))
    )
    (net (code "69") (name "/HALL9_VCC") (class "Default")
      (node (ref "A139_HALL9") (pin "P$1") (pinfunction "P$1_P$1") (pintype "bidirectional"))
      (node (ref "A139_HALL9") (pin "P$6") (pinfunction "P$6_P$6") (pintype "bidirectional"))
      (node (ref "C15") (pin "1") (pinfunction "1_1") (pintype "passive"))
      (node (ref "HALL9_HEADER") (pin "P$2") (pinfunction "2_P$2") (pintype "passive"))
    )
    (net (code "70") (name "/HALL9_VOUT") (class "Default")
      (node (ref "A139_HALL9") (pin "P$2") (pinfunction "P$2_P$2") (pintype "bidirectional"))
      (node (ref "HALL9_HEADER") (pin "P$3") (pinfunction "3_P$3") (pintype "passive"))
    )
    (net (code "71") (name "/HALL9_~{SLEEP_IN}") (class "Default")
      (node (ref "HALL9_HEADER") (pin "P$4") (pinfunction "4_P$4") (pintype "passive"))
      (node (ref "R20") (pin "1") (pinfunction "1_1") (pintype "passive"))
    )
    (net (code "72") (name "/HALL9_~{SLEEP}") (class "Default")
      (node (ref "HALL9") (pin "3") (pinfunction "3_3") (pintype "passive"))
      (node (ref "SHIFT_1") (pin "1") (pinfunction "QB_1") (pintype "tri_state"))
    )
    (net (code "73") (name "/HALL10_GND") (class "Default")
      (node (ref "A139_HALL10") (pin "P$3_4") (pinfunction "P$3_P$3_4") (pintype "bidirectional"))
      (node (ref "C16") (pin "2") (pinfunction "2_2") (pintype "passive"))
      (node (ref "HALL10_HEADER") (pin "P$1") (pinfunction "1_P$1") (pintype "passive"))
    )
    (net (code "74") (name "/HALL10_OUTPUT") (class "Default")
      (node (ref "HALL10") (pin "4") (pinfunction "4_4") (pintype "passive"))
      (node (ref "U$2") (pin "21") (pinfunction "X10_21") (pintype "input"))
    )
    (net (code "75") (name "/HALL10_VCC") (class "Default")
      (node (ref "A139_HALL10") (pin "P$1") (pinfunction "P$1_P$1") (pintype "bidirectional"))
      (node (ref "A139_HALL10") (pin "P$6") (pinfunction "P$6_P$6") (pintype "bidirectional"))
      (node (ref "C16") (pin "1") (pinfunction "1_1") (pintype "passive"))
      (node (ref "HALL10_HEADER") (pin "P$2") (pinfunction "2_P$2") (pintype "passive"))
    )
    (net (code "76") (name "/HALL10_VOUT") (class "Default")
      (node (ref "A139_HALL10") (pin "P$2") (pinfunction "P$2_P$2") (pintype "bidirectional"))
      (node (ref "HALL10_HEADER") (pin "P$3") (pinfunction "3_P$3") (pintype "passive"))
    )
    (net (code "77") (name "/HALL10_~{SLEEP_IN}") (class "Default")
      (node (ref "HALL10_HEADER") (pin "P$4") (pinfunction "4_P$4") (pintype "passive"))
      (node (ref "R21") (pin "1") (pinfunction "1_1") (pintype "passive"))
    )
    (net (code "78") (name "/HALL10_~{SLEEP}") (class "Default")
      (node (ref "HALL10") (pin "3") (pinfunction "3_3") (pintype "passive"))
      (node (ref "SHIFT_1") (pin "2") (pinfunction "QC_2") (pintype "tri_state"))
    )
    (net (code "79") (name "/HALL11_GND") (class "Default")
      (node (ref "A139_HALL11") (pin "P$3_4") (pinfunction "P$3_P$3_4") (pintype "bidirectional"))
      (node (ref "C17") (pin "2") (pinfunction "2_2") (pintype "passive"))
      (node (ref "HALL11_HEADER") (pin "P$1") (pinfunction "1_P$1") (pintype "passive"))
    )
    (net (code "80") (name "/HALL11_OUTPUT") (class "Default")
      (node (ref "HALL11") (pin "4") (pinfunction "4_4") (pintype "passive"))
      (node (ref "U$2") (pin "20") (pinfunction "X11_20") (pintype "input"))
    )
    (net (code "81") (name "/HALL11_VCC") (class "Default")
      (node (ref "A139_HALL11") (pin "P$1") (pinfunction "P$1_P$1") (pintype "bidirectional"))
      (node (ref "A139_HALL11") (pin "P$6") (pinfunction "P$6_P$6") (pintype "bidirectional"))
      (node (ref "C17") (pin "1") (pinfunction "1_1") (pintype "passive"))
      (node (ref "HALL11_HEADER") (pin "P$2") (pinfunction "2_P$2") (pintype "passive"))
    )
    (net (code "82") (name "/HALL11_VOUT") (class "Default")
      (node (ref "A139_HALL11") (pin "P$2") (pinfunction "P$2_P$2") (pintype "bidirectional"))
      (node (ref "HALL11_HEADER") (pin "P$3") (pinfunction "3_P$3") (pintype "passive"))
    )
    (net (code "83") (name "/HALL11_~{SLEEP_IN}") (class "Default")
      (node (ref "HALL11_HEADER") (pin "P$4") (pinfunction "4_P$4") (pintype "passive"))
      (node (ref "R22") (pin "1") (pinfunction "1_1") (pintype "passive"))
    )
    (net (code "84") (name "/HALL11_~{SLEEP}") (class "Default")
      (node (ref "HALL11") (pin "3") (pinfunction "3_3") (pintype "passive"))
      (node (ref "SHIFT_1") (pin "3") (pinfunction "QD_3") (pintype "tri_state"))
    )
    (net (code "85") (name "/HALL12_GND") (class "Default")
      (node (ref "A139_HALL12") (pin "P$3_4") (pinfunction "P$3_P$3_4") (pintype "bidirectional"))
      (node (ref "C18") (pin "2") (pinfunction "2_2") (pintype "passive"))
      (node (ref "HALL12_HEADER") (pin "P$1") (pinfunction "1_P$1") (pintype "passive"))
    )
    (net (code "86") (name "/HALL12_OUTPUT") (class "Default")
      (node (ref "HALL12") (pin "4") (pinfunction "4_4") (pintype "passive"))
      (node (ref "U$2") (pin "19") (pinfunction "X12_19") (pintype "input"))
    )
    (net (code "87") (name "/HALL12_VCC") (class "Default")
      (node (ref "A139_HALL12") (pin "P$1") (pinfunction "P$1_P$1") (pintype "bidirectional"))
      (node (ref "A139_HALL12") (pin "P$6") (pinfunction "P$6_P$6") (pintype "bidirectional"))
      (node (ref "C18") (pin "1") (pinfunction "1_1") (pintype "passive"))
      (node (ref "HALL12_HEADER") (pin "P$2") (pinfunction "2_P$2") (pintype "passive"))
    )
    (net (code "88") (name "/HALL12_VOUT") (class "Default")
      (node (ref "A139_HALL12") (pin "P$2") (pinfunction "P$2_P$2") (pintype "bidirectional"))
      (node (ref "HALL12_HEADER") (pin "P$3") (pinfunction "3_P$3") (pintype "passive"))
    )
    (net (code "89") (name "/HALL12_~{SLEEP_IN}") (class "Default")
      (node (ref "HALL12_HEADER") (pin "P$4") (pinfunction "4_P$4") (pintype "passive"))
      (node (ref "R23") (pin "1") (pinfunction "1_1") (pintype "passive"))
    )
    (net (code "90") (name "/HALL12_~{SLEEP}") (class "Default")
      (node (ref "HALL12") (pin "3") (pinfunction "3_3") (pintype "passive"))
      (node (ref "SHIFT_1") (pin "4") (pinfunction "QE_4") (pintype "tri_state"))
    )
    (net (code "91") (name "/HALL13_GND") (class "Default")
      (node (ref "A139_HALL13") (pin "P$3_4") (pinfunction "P$3_P$3_4") (pintype "bidirectional"))
      (node (ref "C21") (pin "2") (pinfunction "2_2") (pintype "passive"))
      (node (ref "HALL13_HEADER") (pin "P$1") (pinfunction "1_P$1") (pintype "passive"))
    )
    (net (code "92") (name "/HALL13_OUTPUT") (class "Default")
      (node (ref "HALL13") (pin "4") (pinfunction "4_4") (pintype "passive"))
      (node (ref "U$2") (pin "18") (pinfunction "X13_18") (pintype "input"))
    )
    (net (code "93") (name "/HALL13_VCC") (class "Default")
      (node (ref "A139_HALL13") (pin "P$1") (pinfunction "P$1_P$1") (pintype "bidirectional"))
      (node (ref "A139_HALL13") (pin "P$6") (pinfunction "P$6_P$6") (pintype "bidirectional"))
      (node (ref "C21") (pin "1") (pinfunction "1_1") (pintype "passive"))
      (node (ref "HALL13_HEADER") (pin "P$2") (pinfunction "2_P$2") (pintype "passive"))
    )
    (net (code "94") (name "/HALL13_VOUT") (class "Default")
      (node (ref "A139_HALL13") (pin "P$2") (pinfunction "P$2_P$2") (pintype "bidirectional"))
      (node (ref "HALL13_HEADER") (pin "P$3") (pinfunction "3_P$3") (pintype "passive"))
    )
    (net (code "95") (name "/HALL13_~{SLEEP_IN}") (class "Default")
      (node (ref "HALL13_HEADER") (pin "P$4") (pinfunction "4_P$4") (pintype "passive"))
      (node (ref "R25") (pin "1") (pinfunction "1_1") (pintype "passive"))
    )
    (net (code "96") (name "/HALL13_~{SLEEP}") (class "Default")
      (node (ref "HALL13") (pin "3") (pinfunction "3_3") (pintype "passive"))
      (node (ref "SHIFT_1") (pin "5") (pinfunction "QF_5") (pintype "tri_state"))
    )
    (net (code "97") (name "/HALL14_GND") (class "Default")
      (node (ref "A139_HALL14") (pin "P$3_4") (pinfunction "P$3_P$3_4") (pintype "bidirectional"))
      (node (ref "C22") (pin "2") (pinfunction "2_2") (pintype "passive"))
      (node (ref "HALL14_HEADER") (pin "P$1") (pinfunction "1_P$1") (pintype "passive"))
    )
    (net (code "98") (name "/HALL14_OUTPUT") (class "Default")
      (node (ref "HALL14") (pin "4") (pinfunction "4_4") (pintype "passive"))
      (node (ref "U$2") (pin "17") (pinfunction "X14_17") (pintype "input"))
    )
    (net (code "99") (name "/HALL14_VCC") (class "Default")
      (node (ref "A139_HALL14") (pin "P$1") (pinfunction "P$1_P$1") (pintype "bidirectional"))
      (node (ref "A139_HALL14") (pin "P$6") (pinfunction "P$6_P$6") (pintype "bidirectional"))
      (node (ref "C22") (pin "1") (pinfunction "1_1") (pintype "passive"))
      (node (ref "HALL14_HEADER") (pin "P$2") (pinfunction "2_P$2") (pintype "passive"))
    )
    (net (code "100") (name "/HALL14_VOUT") (class "Default")
      (node (ref "A139_HALL14") (pin "P$2") (pinfunction "P$2_P$2") (pintype "bidirectional"))
      (node (ref "HALL14_HEADER") (pin "P$3") (pinfunction "3_P$3") (pintype "passive"))
    )
    (net (code "101") (name "/HALL14_~{SLEEP_IN}") (class "Default")
      (node (ref "HALL14_HEADER") (pin "P$4") (pinfunction "4_P$4") (pintype "passive"))
      (node (ref "R26") (pin "1") (pinfunction "1_1") (pintype "passive"))
    )
    (net (code "102") (name "/HALL14_~{SLEEP}") (class "Default")
      (node (ref "HALL14") (pin "3") (pinfunction "3_3") (pintype "passive"))
      (node (ref "SHIFT_1") (pin "6") (pinfunction "QG_6") (pintype "tri_state"))
    )
    (net (code "103") (name "/HALL15_GND") (class "Default")
      (node (ref "A139_HALL15") (pin "P$3_4") (pinfunction "P$3_P$3_4") (pintype "bidirectional"))
      (node (ref "C24") (pin "2") (pinfunction "2_2") (pintype "passive"))
      (node (ref "HALL15_HEADER") (pin "P$1") (pinfunction "1_P$1") (pintype "passive"))
    )
    (net (code "104") (name "/HALL15_OUTPUT") (class "Default")
      (node (ref "HALL15") (pin "4") (pinfunction "4_4") (pintype "passive"))
      (node (ref "U$2") (pin "16") (pinfunction "X15_16") (pintype "input"))
    )
    (net (code "105") (name "/HALL15_VCC") (class "Default")
      (node (ref "A139_HALL15") (pin "P$1") (pinfunction "P$1_P$1") (pintype "bidirectional"))
      (node (ref "A139_HALL15") (pin "P$6") (pinfunction "P$6_P$6") (pintype "bidirectional"))
      (node (ref "C24") (pin "1") (pinfunction "1_1") (pintype "passive"))
      (node (ref "HALL15_HEADER") (pin "P$2") (pinfunction "2_P$2") (pintype "passive"))
    )
    (net (code "106") (name "/HALL15_VOUT") (class "Default")
      (node (ref "A139_HALL15") (pin "P$2") (pinfunction "P$2_P$2") (pintype "bidirectional"))
      (node (ref "HALL15_HEADER") (pin "P$3") (pinfunction "3_P$3") (pintype "passive"))
    )
    (net (code "107") (name "/HALL15_~{SLEEP_IN}") (class "Default")
      (node (ref "HALL15_HEADER") (pin "P$4") (pinfunction "4_P$4") (pintype "passive"))
      (node (ref "R27") (pin "1") (pinfunction "1_1") (pintype "passive"))
    )
    (net (code "108") (name "/HALL15_~{SLEEP}") (class "Default")
      (node (ref "HALL15") (pin "3") (pinfunction "3_3") (pintype "passive"))
      (node (ref "SHIFT_1") (pin "7") (pinfunction "QH_7") (pintype "tri_state"))
    )
    (net (code "109") (name "/LED_GRN") (class "Default")
      (node (ref "R2") (pin "2") (pinfunction "2_2") (pintype "passive"))
      (node (ref "U1") (pin "26") (pinfunction "PC3(ADC3)_26") (pintype "bidirectional"))
    )
    (net (code "110") (name "/LED_RED") (class "Default")
      (node (ref "R1") (pin "2") (pinfunction "2_2") (pintype "passive"))
      (node (ref "U1") (pin "2") (pinfunction "PD4(XCK/T0)_2") (pintype "bidirectional"))
    )
    (net (code "111") (name "/MISO") (class "Default")
      (node (ref "J1") (pin "1") (pinfunction "1_1") (pintype "passive"))
      (node (ref "U$1") (pin "MISO7") (pinfunction "DATA_OUT_MISO_MISO7") (pintype "output"))
      (node (ref "U1") (pin "16") (pinfunction "PB4(MISO)_16") (pintype "bidirectional"))
    )
    (net (code "112") (name "/MOSI") (class "Default")
      (node (ref "J1") (pin "4") (pinfunction "4_4") (pintype "passive"))
      (node (ref "SHIFT_0") (pin "14") (pinfunction "SER_14") (pintype "input"))
      (node (ref "U$1") (pin "MOSI3") (pinfunction "DATA_IN_MOSI_MOSI3") (pintype "input"))
      (node (ref "U1") (pin "15") (pinfunction "PB3(MOSI/OC2)_15") (pintype "bidirectional"))
    )
    (net (code "113") (name "/MUX_S0") (class "Default")
      (node (ref "U$2") (pin "10") (pinfunction "S0_10") (pintype "input"))
      (node (ref "U1") (pin "13") (pinfunction "PB1(OC1A)_13") (pintype "bidirectional"))
    )
    (net (code "114") (name "/MUX_S1") (class "Default")
      (node (ref "U$2") (pin "11") (pinfunction "S1_11") (pintype "input"))
      (node (ref "U1") (pin "9") (pinfunction "PD5(T1)_9") (pintype "bidirectional"))
    )
    (net (code "115") (name "/MUX_S2") (class "Default")
      (node (ref "U$2") (pin "14") (pinfunction "S2_14") (pintype "input"))
      (node (ref "U1") (pin "10") (pinfunction "PD6(AIN0)_10") (pintype "bidirectional"))
    )
    (net (code "116") (name "/MUX_S3") (class "Default")
      (node (ref "U$2") (pin "13") (pinfunction "S3_13") (pintype "input"))
      (node (ref "U1") (pin "11") (pinfunction "PD7(AIN1)_11") (pintype "bidirectional"))
    )
    (net (code "117") (name "/MUX_~{EN}") (class "Default")
      (node (ref "R28") (pin "1") (pinfunction "1_1") (pintype "passive"))
      (node (ref "U$2") (pin "15") (pinfunction "~{E}_15") (pintype "input"))
      (node (ref "U1") (pin "12") (pinfunction "PB0(ICP)_12") (pintype "bidirectional"))
    )
    (net (code "118") (name "/RESET") (class "Default")
      (node (ref "C5") (pin "2") (pinfunction "2_2") (pintype "passive"))
      (node (ref "J1") (pin "5") (pinfunction "5_5") (pintype "passive"))
      (node (ref "R6") (pin "1") (pinfunction "1_1") (pintype "passive"))
      (node (ref "RESET") (pin "S$1") (pinfunction "S1_S$1") (pintype "passive"))
      (node (ref "U1") (pin "29") (pinfunction "PC6(/RESET)_29") (pintype "bidirectional"))
    )
    (net (code "119") (name "/SCK") (class "Default")
      (node (ref "J1") (pin "3") (pinfunction "3_3") (pintype "passive"))
      (node (ref "SHIFT_0") (pin "11") (pinfunction "SRCLK_11") (pintype "input"))
      (node (ref "SHIFT_1") (pin "11") (pinfunction "SRCLK_11") (pintype "input"))
      (node (ref "U$1") (pin "SCK5") (pinfunction "SCLK_SCK5") (pintype "input"))
      (node (ref "U1") (pin "17") (pinfunction "PB5(SCK)_17") (pintype "bidirectional"))
    )
    (net (code "120") (name "/SCL") (class "Default")
      (node (ref "DS3231M") (pin "8") (pinfunction "P$8_SCL_8") (pintype "bidirectional"))
      (node (ref "I2C_HEADER") (pin "3") (pinfunction "3_3") (pintype "passive"))
      (node (ref "R7") (pin "1") (pinfunction "1_1") (pintype "passive"))
      (node (ref "U1") (pin "28") (pinfunction "PC5(ADC5/SCL)_28") (pintype "bidirectional"))
    )
    (net (code "121") (name "/SDA") (class "Default")
      (node (ref "DS3231M") (pin "7") (pinfunction "P$7_SDA_7") (pintype "bidirectional"))
      (node (ref "I2C_HEADER") (pin "4") (pinfunction "4_4") (pintype "passive"))
      (node (ref "R8") (pin "1") (pinfunction "1_1") (pintype "passive"))
      (node (ref "U1") (pin "27") (pinfunction "PC4(ADC4/SDA)_27") (pintype "bidirectional"))
    )
    (net (code "122") (name "/SHIFT_CLEAR") (class "Default")
      (node (ref "R14") (pin "1") (pinfunction "1_1") (pintype "passive"))
      (node (ref "SHIFT_0") (pin "10") (pinfunction "~{SRCLR}_10") (pintype "input"))
      (node (ref "SHIFT_1") (pin "10") (pinfunction "~{SRCLR}_10") (pintype "input"))
      (node (ref "U1") (pin "24") (pinfunction "PC1(ADC1)_24") (pintype "bidirectional"))
    )
    (net (code "123") (name "/TO_FTDI_RX") (class "Default")
      (node (ref "JP1") (pin "5") (pinfunction "5_5") (pintype "passive"))
      (node (ref "U1") (pin "31") (pinfunction "PD1(TXD)_31") (pintype "bidirectional"))
    )
    (net (code "124") (name "/TO_FTDI_TX") (class "Default")
      (node (ref "JP1") (pin "4") (pinfunction "4_4") (pintype "passive"))
      (node (ref "U1") (pin "30") (pinfunction "PD0(RXD)_30") (pintype "bidirectional"))
    )
    (net (code "125") (name "/VBAT") (class "Default")
      (node (ref "CR1220_BATTERY") (pin "P$1") (pinfunction "VBAT_P$1") (pintype "power_in"))
      (node (ref "CR1220_BATTERY") (pin "P$2") (pinfunction "P$2_P$2") (pintype "power_in"))
      (node (ref "DS3231M") (pin "6") (pinfunction "P$6_VBAT_6") (pintype "bidirectional"))
    )
    (net (code "126") (name "/VRAW") (class "Default")
      (node (ref "C1") (pin "+") (pinfunction "+_+") (pintype "passive"))
      (node (ref "MCP1700T-3302") (pin "3") (pinfunction "VIN_3") (pintype "input"))
      (node (ref "P-FET") (pin "2") (pinfunction "S_2") (pintype "passive"))
      (node (ref "R33") (pin "2") (pinfunction "2_2") (pintype "passive"))
      (node (ref "X1") (pin "2") (pinfunction "S_2") (pintype "passive"))
    )
    (net (code "127") (name "/~{SLEEP0}") (class "Default")
      (node (ref "A139_HALL0") (pin "P$5") (pinfunction "P$5_P$5") (pintype "bidirectional"))
      (node (ref "R16") (pin "2") (pinfunction "2_2") (pintype "passive"))
    )
    (net (code "128") (name "/~{SLEEP1}") (class "Default")
      (node (ref "A139_HALL1") (pin "P$5") (pinfunction "P$5_P$5") (pintype "bidirectional"))
      (node (ref "R11") (pin "2") (pinfunction "2_2") (pintype "passive"))
    )
    (net (code "129") (name "/~{SLEEP2}") (class "Default")
      (node (ref "A139_HALL2") (pin "P$5") (pinfunction "P$5_P$5") (pintype "bidirectional"))
      (node (ref "R10") (pin "2") (pinfunction "2_2") (pintype "passive"))
    )
    (net (code "130") (name "/~{SLEEP3}") (class "Default")
      (node (ref "A139_HALL3") (pin "P$5") (pinfunction "P$5_P$5") (pintype "bidirectional"))
      (node (ref "R12") (pin "2") (pinfunction "2_2") (pintype "passive"))
    )
    (net (code "131") (name "/~{SLEEP4}") (class "Default")
      (node (ref "A139_HALL4") (pin "P$5") (pinfunction "P$5_P$5") (pintype "bidirectional"))
      (node (ref "R13") (pin "2") (pinfunction "2_2") (pintype "passive"))
    )
    (net (code "132") (name "/~{SLEEP5}") (class "Default")
      (node (ref "A139_HALL5") (pin "P$5") (pinfunction "P$5_P$5") (pintype "bidirectional"))
      (node (ref "R17") (pin "2") (pinfunction "2_2") (pintype "passive"))
    )
    (net (code "133") (name "/~{SLEEP6}") (class "Default")
      (node (ref "A139_HALL6") (pin "P$5") (pinfunction "P$5_P$5") (pintype "bidirectional"))
      (node (ref "R18") (pin "2") (pinfunction "2_2") (pintype "passive"))
    )
    (net (code "134") (name "/~{SLEEP7}") (class "Default")
      (node (ref "A139_HALL7") (pin "P$5") (pinfunction "P$5_P$5") (pintype "bidirectional"))
      (node (ref "R19") (pin "2") (pinfunction "2_2") (pintype "passive"))
    )
    (net (code "135") (name "/~{SLEEP8}") (class "Default")
      (node (ref "A139_HALL8") (pin "P$5") (pinfunction "P$5_P$5") (pintype "bidirectional"))
      (node (ref "R24") (pin "2") (pinfunction "2_2") (pintype "passive"))
    )
    (net (code "136") (name "/~{SLEEP9}") (class "Default")
      (node (ref "A139_HALL9") (pin "P$5") (pinfunction "P$5_P$5") (pintype "bidirectional"))
      (node (ref "R20") (pin "2") (pinfunction "2_2") (pintype "passive"))
    )
    (net (code "137") (name "/~{SLEEP10}") (class "Default")
      (node (ref "A139_HALL10") (pin "P$5") (pinfunction "P$5_P$5") (pintype "bidirectional"))
      (node (ref "R21") (pin "2") (pinfunction "2_2") (pintype "passive"))
    )
    (net (code "138") (name "/~{SLEEP11}") (class "Default")
      (node (ref "A139_HALL11") (pin "P$5") (pinfunction "P$5_P$5") (pintype "bidirectional"))
      (node (ref "R22") (pin "2") (pinfunction "2_2") (pintype "passive"))
    )
    (net (code "139") (name "/~{SLEEP12}") (class "Default")
      (node (ref "A139_HALL12") (pin "P$5") (pinfunction "P$5_P$5") (pintype "bidirectional"))
      (node (ref "R23") (pin "2") (pinfunction "2_2") (pintype "passive"))
    )
    (net (code "140") (name "/~{SLEEP13}") (class "Default")
      (node (ref "A139_HALL13") (pin "P$5") (pinfunction "P$5_P$5") (pintype "bidirectional"))
      (node (ref "R25") (pin "2") (pinfunction "2_2") (pintype "passive"))
    )
    (net (code "141") (name "/~{SLEEP14}") (class "Default")
      (node (ref "A139_HALL14") (pin "P$5") (pinfunction "P$5_P$5") (pintype "bidirectional"))
      (node (ref "R26") (pin "2") (pinfunction "2_2") (pintype "passive"))
    )
    (net (code "142") (name "/~{SLEEP15}") (class "Default")
      (node (ref "A139_HALL15") (pin "P$5") (pinfunction "P$5_P$5") (pintype "bidirectional"))
      (node (ref "R27") (pin "2") (pinfunction "2_2") (pintype "passive"))
    )
    (net (code "143") (name "GND") (class "Default")
      (node (ref "BJT") (pin "2") (pinfunction "E_2") (pintype "passive"))
      (node (ref "BUTTON0") (pin "S$1") (pinfunction "S1_S$1") (pintype "passive"))
      (node (ref "BUTTON1") (pin "S$1") (pinfunction "S1_S$1") (pintype "passive"))
      (node (ref "C1") (pin "-") (pinfunction "-_-") (pintype "passive"))
      (node (ref "C2") (pin "-") (pinfunction "-_-") (pintype "passive"))
      (node (ref "C3") (pin "2") (pinfunction "2_2") (pintype "passive"))
      (node (ref "C4") (pin "2") (pinfunction "2_2") (pintype "passive"))
      (node (ref "C6") (pin "2") (pinfunction "2_2") (pintype "passive"))
      (node (ref "C7") (pin "2") (pinfunction "2_2") (pintype "passive"))
      (node (ref "C8") (pin "2") (pinfunction "2_2") (pintype "passive"))
      (node (ref "C9") (pin "2") (pinfunction "2_2") (pintype "passive"))
      (node (ref "CR1220_BATTERY") (pin "GND") (pinfunction "GND_GND") (pintype "power_in"))
      (node (ref "DS3231M") (pin "5") (pinfunction "P$5_GND_5") (pintype "power_in"))
      (node (ref "GROUND_CON") (pin "1") (pinfunction "P$1_1") (pintype "bidirectional"))
      (node (ref "I2C_HEADER") (pin "2") (pinfunction "2_2") (pintype "passive"))
      (node (ref "J1") (pin "6") (pinfunction "6_6") (pintype "passive"))
      (node (ref "JP1") (pin "1") (pinfunction "1_1") (pintype "passive"))
      (node (ref "JP1") (pin "2") (pinfunction "2_2") (pintype "passive"))
      (node (ref "LED1") (pin "C") (pinfunction "C_C") (pintype "passive"))
      (node (ref "LED2") (pin "C") (pinfunction "C_C") (pintype "passive"))
      (node (ref "MCP1700T-3302") (pin "1") (pinfunction "GND_1") (pintype "passive"))
      (node (ref "R29") (pin "1") (pinfunction "1_1") (pintype "passive"))
      (node (ref "R3") (pin "1") (pinfunction "1_1") (pintype "passive"))
      (node (ref "R32") (pin "1") (pinfunction "1_1") (pintype "passive"))
      (node (ref "RESET") (pin "P$1") (pinfunction "P1_P$1") (pintype "passive"))
      (node (ref "SHIFT_0") (pin "13") (pinfunction "~{OE}_13") (pintype "input"))
      (node (ref "SHIFT_0") (pin "8") (pinfunction "GND_8") (pintype "power_in"))
      (node (ref "SHIFT_1") (pin "13") (pinfunction "~{OE}_13") (pintype "input"))
      (node (ref "SHIFT_1") (pin "8") (pinfunction "GND_8") (pintype "power_in"))
      (node (ref "U$1") (pin "GND6") (pinfunction "VSS_GND_GND6") (pintype "power_in"))
      (node (ref "U$1") (pin "MNT1") (pinfunction "GND1_MNT1") (pintype "power_in"))
      (node (ref "U$1") (pin "MNT2") (pinfunction "GND2_MNT2") (pintype "power_in"))
      (node (ref "U$1") (pin "MNT3") (pinfunction "GND3_MNT3") (pintype "power_in"))
      (node (ref "U$1") (pin "MNT4") (pinfunction "GND4_MNT4") (pintype "power_in"))
      (node (ref "U$2") (pin "12") (pinfunction "GND_12") (pintype "power_in"))
      (node (ref "U1") (pin "3") (pinfunction "GND_3") (pintype "bidirectional"))
      (node (ref "U1") (pin "5") (pinfunction "GND_5") (pintype "bidirectional"))
      (node (ref "X1") (pin "1") (pinfunction "S_1") (pintype "passive"))
    )
    (net (code "144") (name "Net-(BJT-B)") (class "Default")
      (node (ref "BJT") (pin "1") (pinfunction "B_1") (pintype "passive"))
      (node (ref "R31") (pin "2") (pinfunction "2_2") (pintype "passive"))
    )
    (net (code "145") (name "Net-(LED1-PadA)") (class "Default")
      (node (ref "LED1") (pin "A") (pinfunction "A_A") (pintype "passive"))
      (node (ref "R1") (pin "1") (pinfunction "1_1") (pintype "passive"))
    )
    (net (code "146") (name "Net-(LED2-PadA)") (class "Default")
      (node (ref "LED2") (pin "A") (pinfunction "A_A") (pintype "passive"))
      (node (ref "R2") (pin "1") (pinfunction "1_1") (pintype "passive"))
    )
    (net (code "147") (name "Net-(P-FET-D)") (class "Default")
      (node (ref "P-FET") (pin "3") (pinfunction "D_3") (pintype "passive"))
      (node (ref "R30") (pin "2") (pinfunction "2_2") (pintype "passive"))
    )
    (net (code "148") (name "Net-(SHIFT_0-QH*)") (class "Default")
      (node (ref "SHIFT_0") (pin "9") (pinfunction "QH*_9") (pintype "tri_state"))
      (node (ref "SHIFT_1") (pin "14") (pinfunction "SER_14") (pintype "input"))
    )
    (net (code "149") (name "Net-(U$1-DAT1_NC)") (class "Default")
      (node (ref "R5") (pin "1") (pinfunction "1_1") (pintype "passive"))
      (node (ref "U$1") (pin "NC1") (pinfunction "DAT1_NC_NC1") (pintype "bidirectional"))
    )
    (net (code "150") (name "Net-(U$1-DAT2_RES)") (class "Default")
      (node (ref "R4") (pin "1") (pinfunction "1_1") (pintype "passive"))
      (node (ref "U$1") (pin "RES8") (pinfunction "DAT2_RES_RES8") (pintype "bidirectional"))
    )
    (net (code "151") (name "Net-(U$17-P$1)") (class "Default")
      (node (ref "U$17") (pin "1") (pinfunction "P$1_1") (pintype "bidirectional"))
      (node (ref "U1") (pin "20") (pinfunction "AREF_20") (pintype "bidirectional"))
    )
    (net (code "152") (name "VCC") (class "Default")
      (node (ref "C2") (pin "+") (pinfunction "+_+") (pintype "passive"))
      (node (ref "C3") (pin "1") (pinfunction "1_1") (pintype "passive"))
      (node (ref "C4") (pin "1") (pinfunction "1_1") (pintype "passive"))
      (node (ref "C6") (pin "1") (pinfunction "1_1") (pintype "passive"))
      (node (ref "C7") (pin "1") (pinfunction "1_1") (pintype "passive"))
      (node (ref "C8") (pin "1") (pinfunction "1_1") (pintype "passive"))
      (node (ref "C9") (pin "1") (pinfunction "1_1") (pintype "passive"))
      (node (ref "DS3231M") (pin "2") (pinfunction "P$2_VCC_2") (pintype "power_in"))
      (node (ref "HALL0") (pin "1") (pinfunction "1_1") (pintype "passive"))
      (node (ref "HALL1") (pin "1") (pinfunction "1_1") (pintype "passive"))
      (node (ref "HALL10") (pin "1") (pinfunction "1_1") (pintype "passive"))
      (node (ref "HALL11") (pin "1") (pinfunction "1_1") (pintype "passive"))
      (node (ref "HALL12") (pin "1") (pinfunction "1_1") (pintype "passive"))
      (node (ref "HALL13") (pin "1") (pinfunction "1_1") (pintype "passive"))
      (node (ref "HALL14") (pin "1") (pinfunction "1_1") (pintype "passive"))
      (node (ref "HALL15") (pin "1") (pinfunction "1_1") (pintype "passive"))
      (node (ref "HALL2") (pin "1") (pinfunction "1_1") (pintype "passive"))
      (node (ref "HALL3") (pin "1") (pinfunction "1_1") (pintype "passive"))
      (node (ref "HALL4") (pin "1") (pinfunction "1_1") (pintype "passive"))
      (node (ref "HALL5") (pin "1") (pinfunction "1_1") (pintype "passive"))
      (node (ref "HALL6") (pin "1") (pinfunction "1_1") (pintype "passive"))
      (node (ref "HALL7") (pin "1") (pinfunction "1_1") (pintype "passive"))
      (node (ref "HALL8") (pin "1") (pinfunction "1_1") (pintype "passive"))
      (node (ref "HALL9") (pin "1") (pinfunction "1_1") (pintype "passive"))
      (node (ref "I2C_HEADER") (pin "1") (pinfunction "1_1") (pintype "passive"))
      (node (ref "INDUCTOR") (pin "P$2") (pinfunction "2_P$2") (pintype "passive"))
      (node (ref "J1") (pin "2") (pinfunction "2_2") (pintype "passive"))
      (node (ref "JP1") (pin "3") (pinfunction "3_3") (pintype "passive"))
      (node (ref "MCP1700T-3302") (pin "2") (pinfunction "VOUT_2") (pintype "output"))
      (node (ref "R14") (pin "2") (pinfunction "2_2") (pintype "passive"))
      (node (ref "R15") (pin "2") (pinfunction "2_2") (pintype "passive"))
      (node (ref "R28") (pin "2") (pinfunction "2_2") (pintype "passive"))
      (node (ref "R4") (pin "2") (pinfunction "2_2") (pintype "passive"))
      (node (ref "R5") (pin "2") (pinfunction "2_2") (pintype "passive"))
      (node (ref "R6") (pin "2") (pinfunction "2_2") (pintype "passive"))
      (node (ref "R7") (pin "2") (pinfunction "2_2") (pintype "passive"))
      (node (ref "R8") (pin "2") (pinfunction "2_2") (pintype "passive"))
      (node (ref "R9") (pin "2") (pinfunction "2_2") (pintype "passive"))
      (node (ref "SHIFT_0") (pin "16") (pinfunction "VCC_16") (pintype "power_in"))
      (node (ref "SHIFT_1") (pin "16") (pinfunction "VCC_16") (pintype "power_in"))
      (node (ref "U$1") (pin "VDD4") (pinfunction "VDD_VDD4") (pintype "power_in"))
      (node (ref "U$2") (pin "24") (pinfunction "VCC_24") (pintype "power_in"))
      (node (ref "U1") (pin "4") (pinfunction "VCC_4") (pintype "bidirectional"))
      (node (ref "U1") (pin "6") (pinfunction "VCC_6") (pintype "bidirectional"))
    )
    (net (code "153") (name "unconnected-(BUTTON0-PadP)") (class "Default")
      (node (ref "BUTTON0") (pin "P") (pinfunction "P_P") (pintype "passive"))
    )
    (net (code "154") (name "unconnected-(BUTTON0-PadS)") (class "Default")
      (node (ref "BUTTON0") (pin "S") (pinfunction "S_S") (pintype "passive"))
    )
    (net (code "155") (name "unconnected-(BUTTON1-PadP)") (class "Default")
      (node (ref "BUTTON1") (pin "P") (pinfunction "P_P") (pintype "passive"))
    )
    (net (code "156") (name "unconnected-(BUTTON1-PadS)") (class "Default")
      (node (ref "BUTTON1") (pin "S") (pinfunction "S_S") (pintype "passive"))
    )
    (net (code "157") (name "unconnected-(DS3231M-P$3_INT-Pad3)") (class "Default")
      (node (ref "DS3231M") (pin "3") (pinfunction "P$3_INT_3") (pintype "bidirectional"))
    )
    (net (code "158") (name "unconnected-(DS3231M-P$4_RST-Pad4)") (class "Default")
      (node (ref "DS3231M") (pin "4") (pinfunction "P$4_RST_4") (pintype "bidirectional"))
    )
    (net (code "159") (name "unconnected-(RESET-PadP)") (class "Default")
      (node (ref "RESET") (pin "P") (pinfunction "P_P") (pintype "passive"))
    )
    (net (code "160") (name "unconnected-(RESET-PadS)") (class "Default")
      (node (ref "RESET") (pin "S") (pinfunction "S_S") (pintype "passive"))
    )
    (net (code "161") (name "unconnected-(SHIFT_1-QH*-Pad9)") (class "Default")
      (node (ref "SHIFT_1") (pin "9") (pinfunction "QH*_9") (pintype "tri_state"))
    )
    (net (code "162") (name "unconnected-(U$1-CARD_DETECT-PadCARD_DETECT1)") (class "Default")
      (node (ref "U$1") (pin "CARD_DETECT1") (pinfunction "CARD_DETECT_CARD_DETECT1") (pintype "passive"))
    )
    (net (code "163") (name "unconnected-(U$1-CARD_DETECT1-PadCARD_DETECT2)") (class "Default")
      (node (ref "U$1") (pin "CARD_DETECT2") (pinfunction "CARD_DETECT1_CARD_DETECT2") (pintype "passive"))
    )
    (net (code "164") (name "unconnected-(U1-PB7(XTAL2{slash}TOSC2)-Pad8)") (class "Default")
      (node (ref "U1") (pin "8") (pinfunction "PB7(XTAL2/TOSC2)_8") (pintype "bidirectional"))
    )
  )
)
